# Battery_Charger.net
KiCad netlist of a schematic drawn in EAGLE
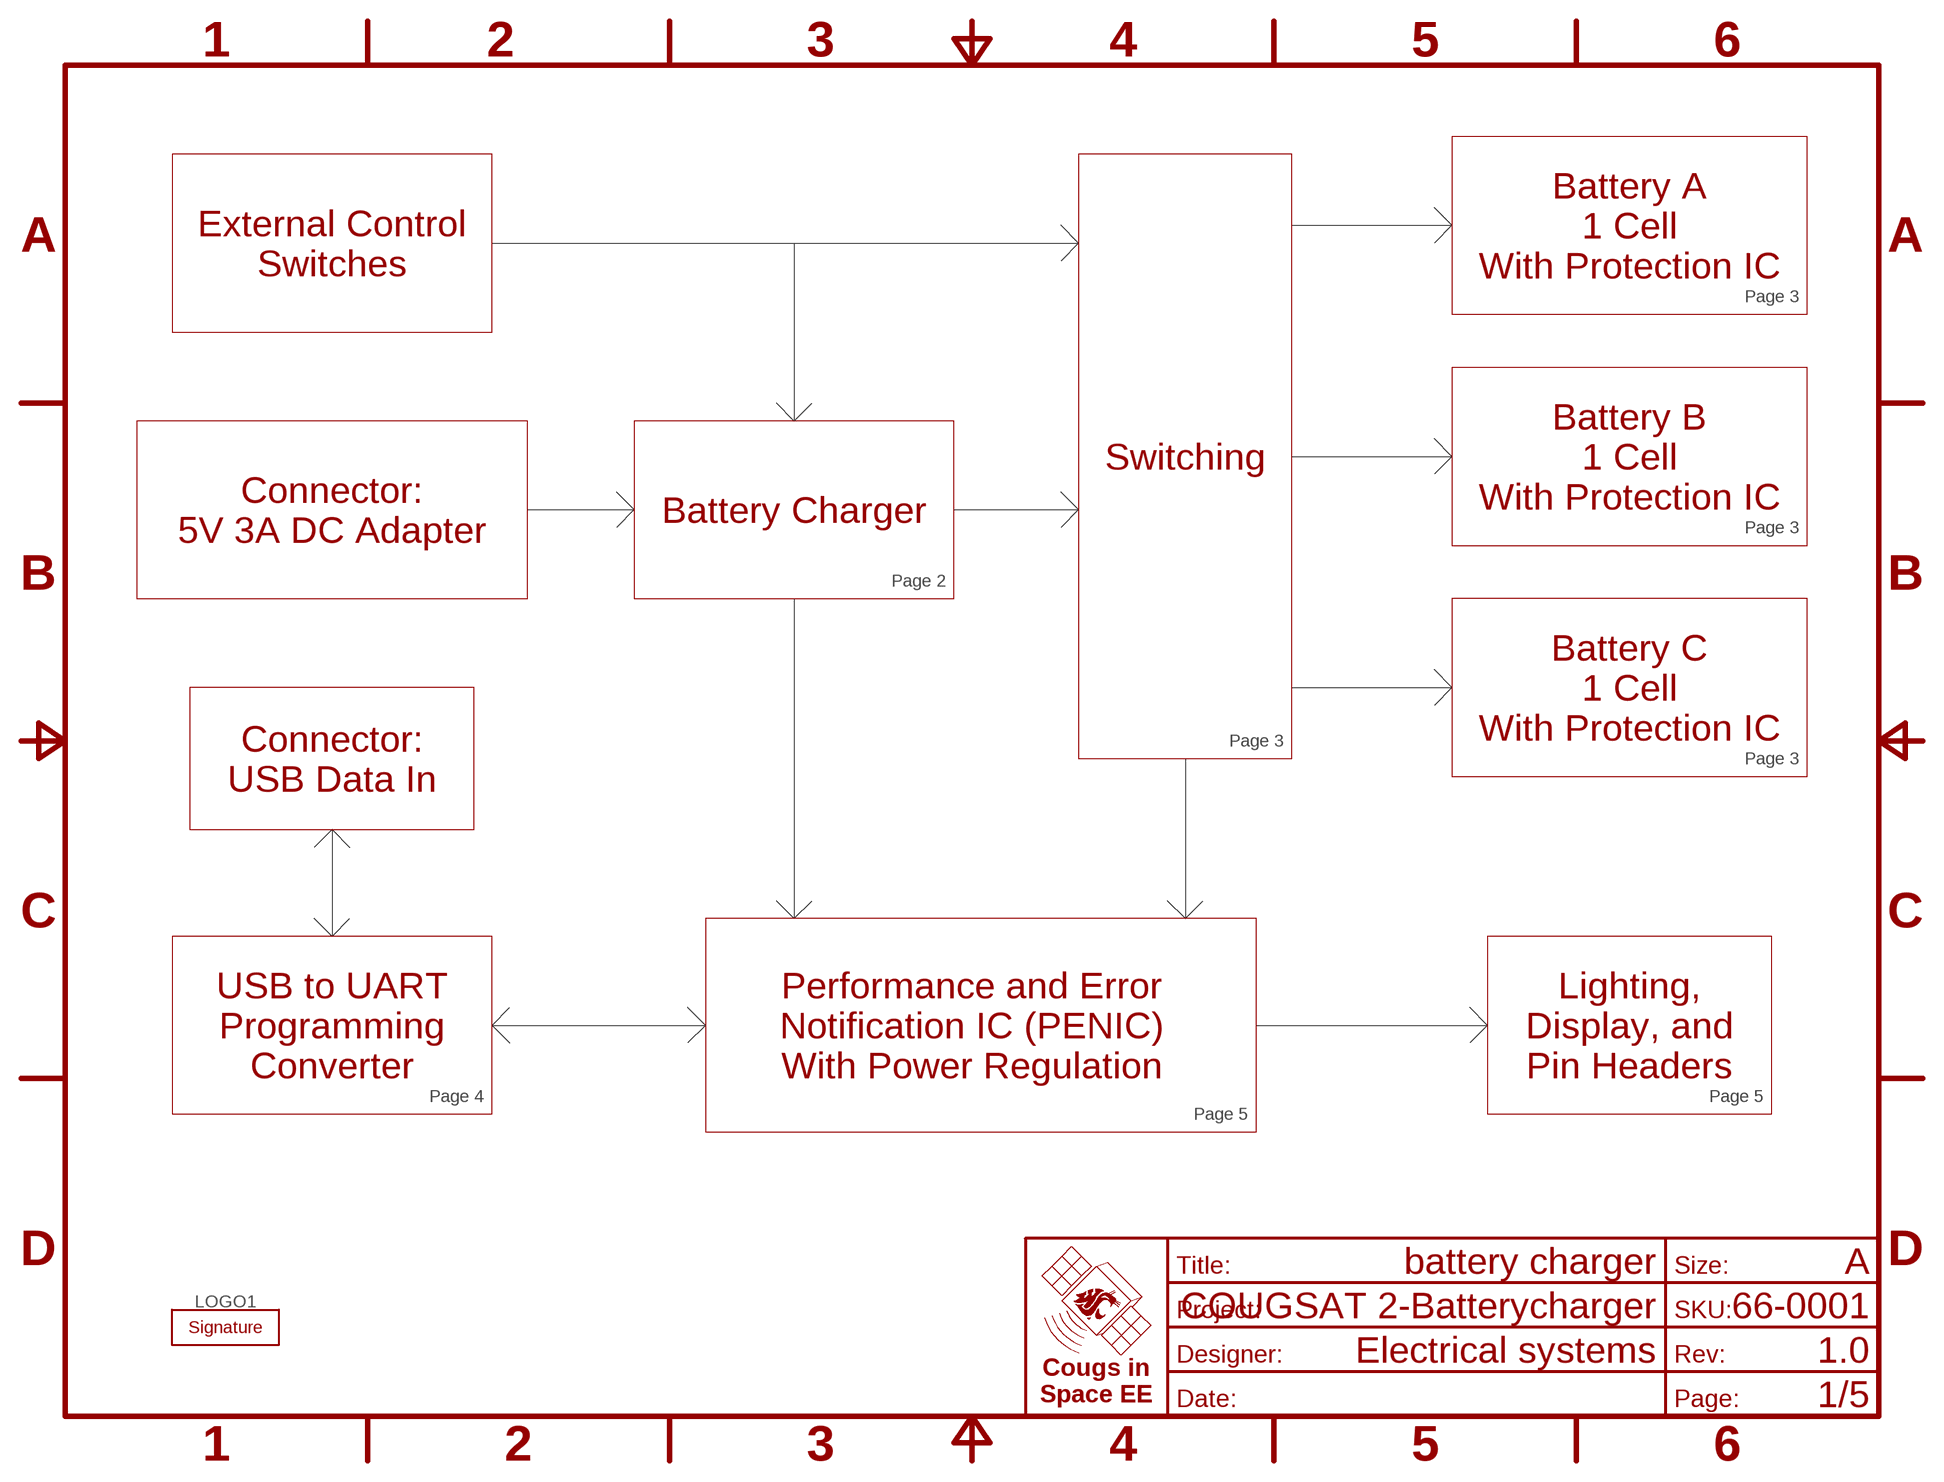
[diagram p0: schematic, sheet 1]
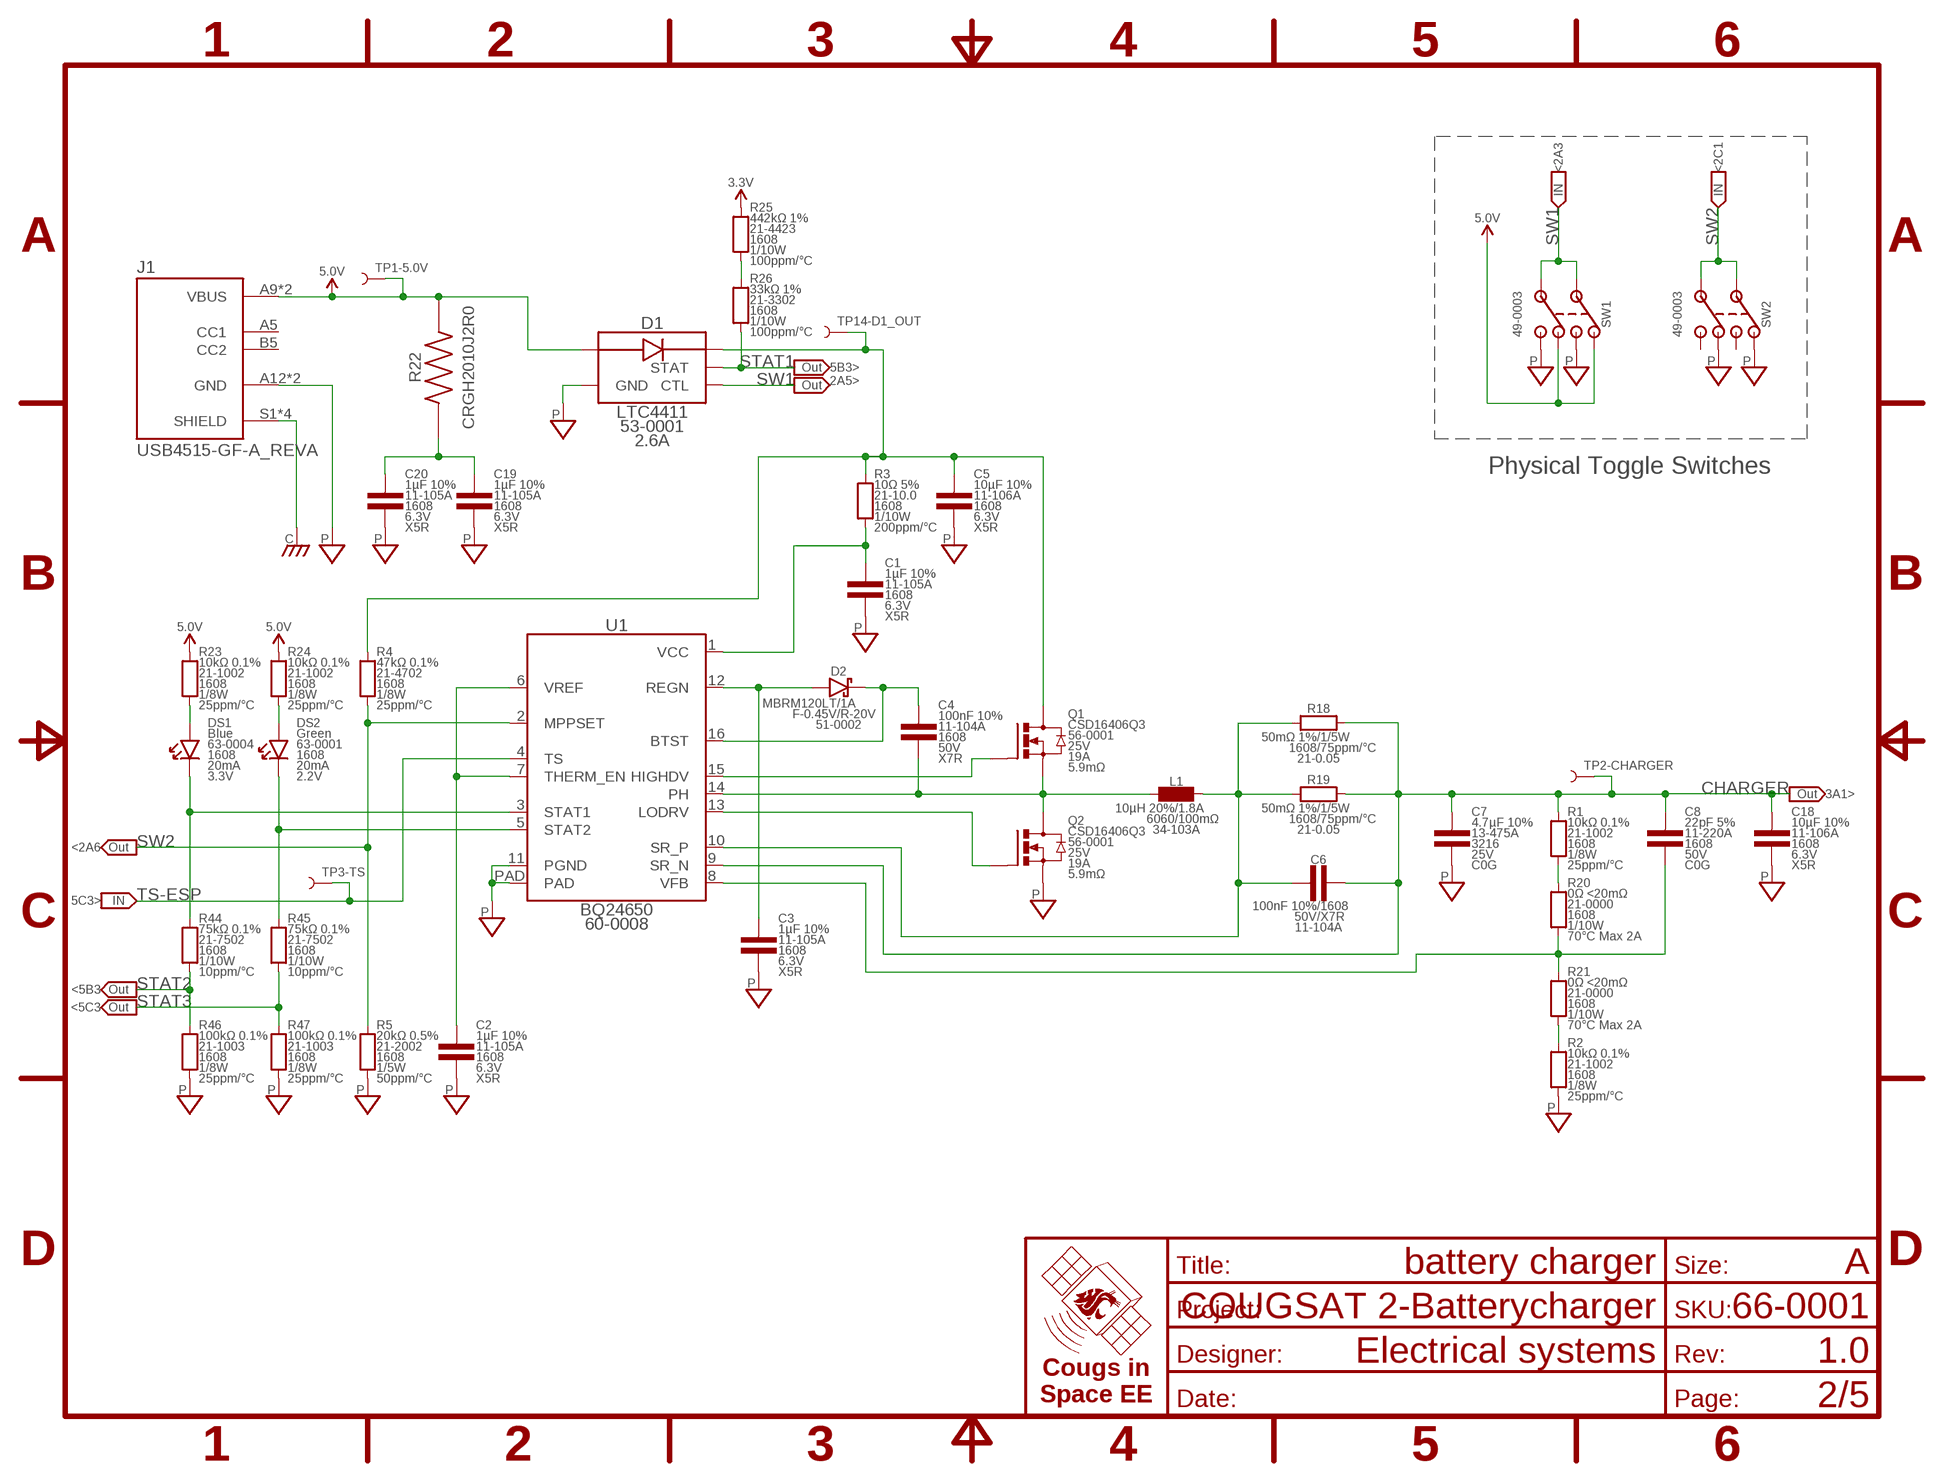
[diagram p1: schematic, sheet 2]
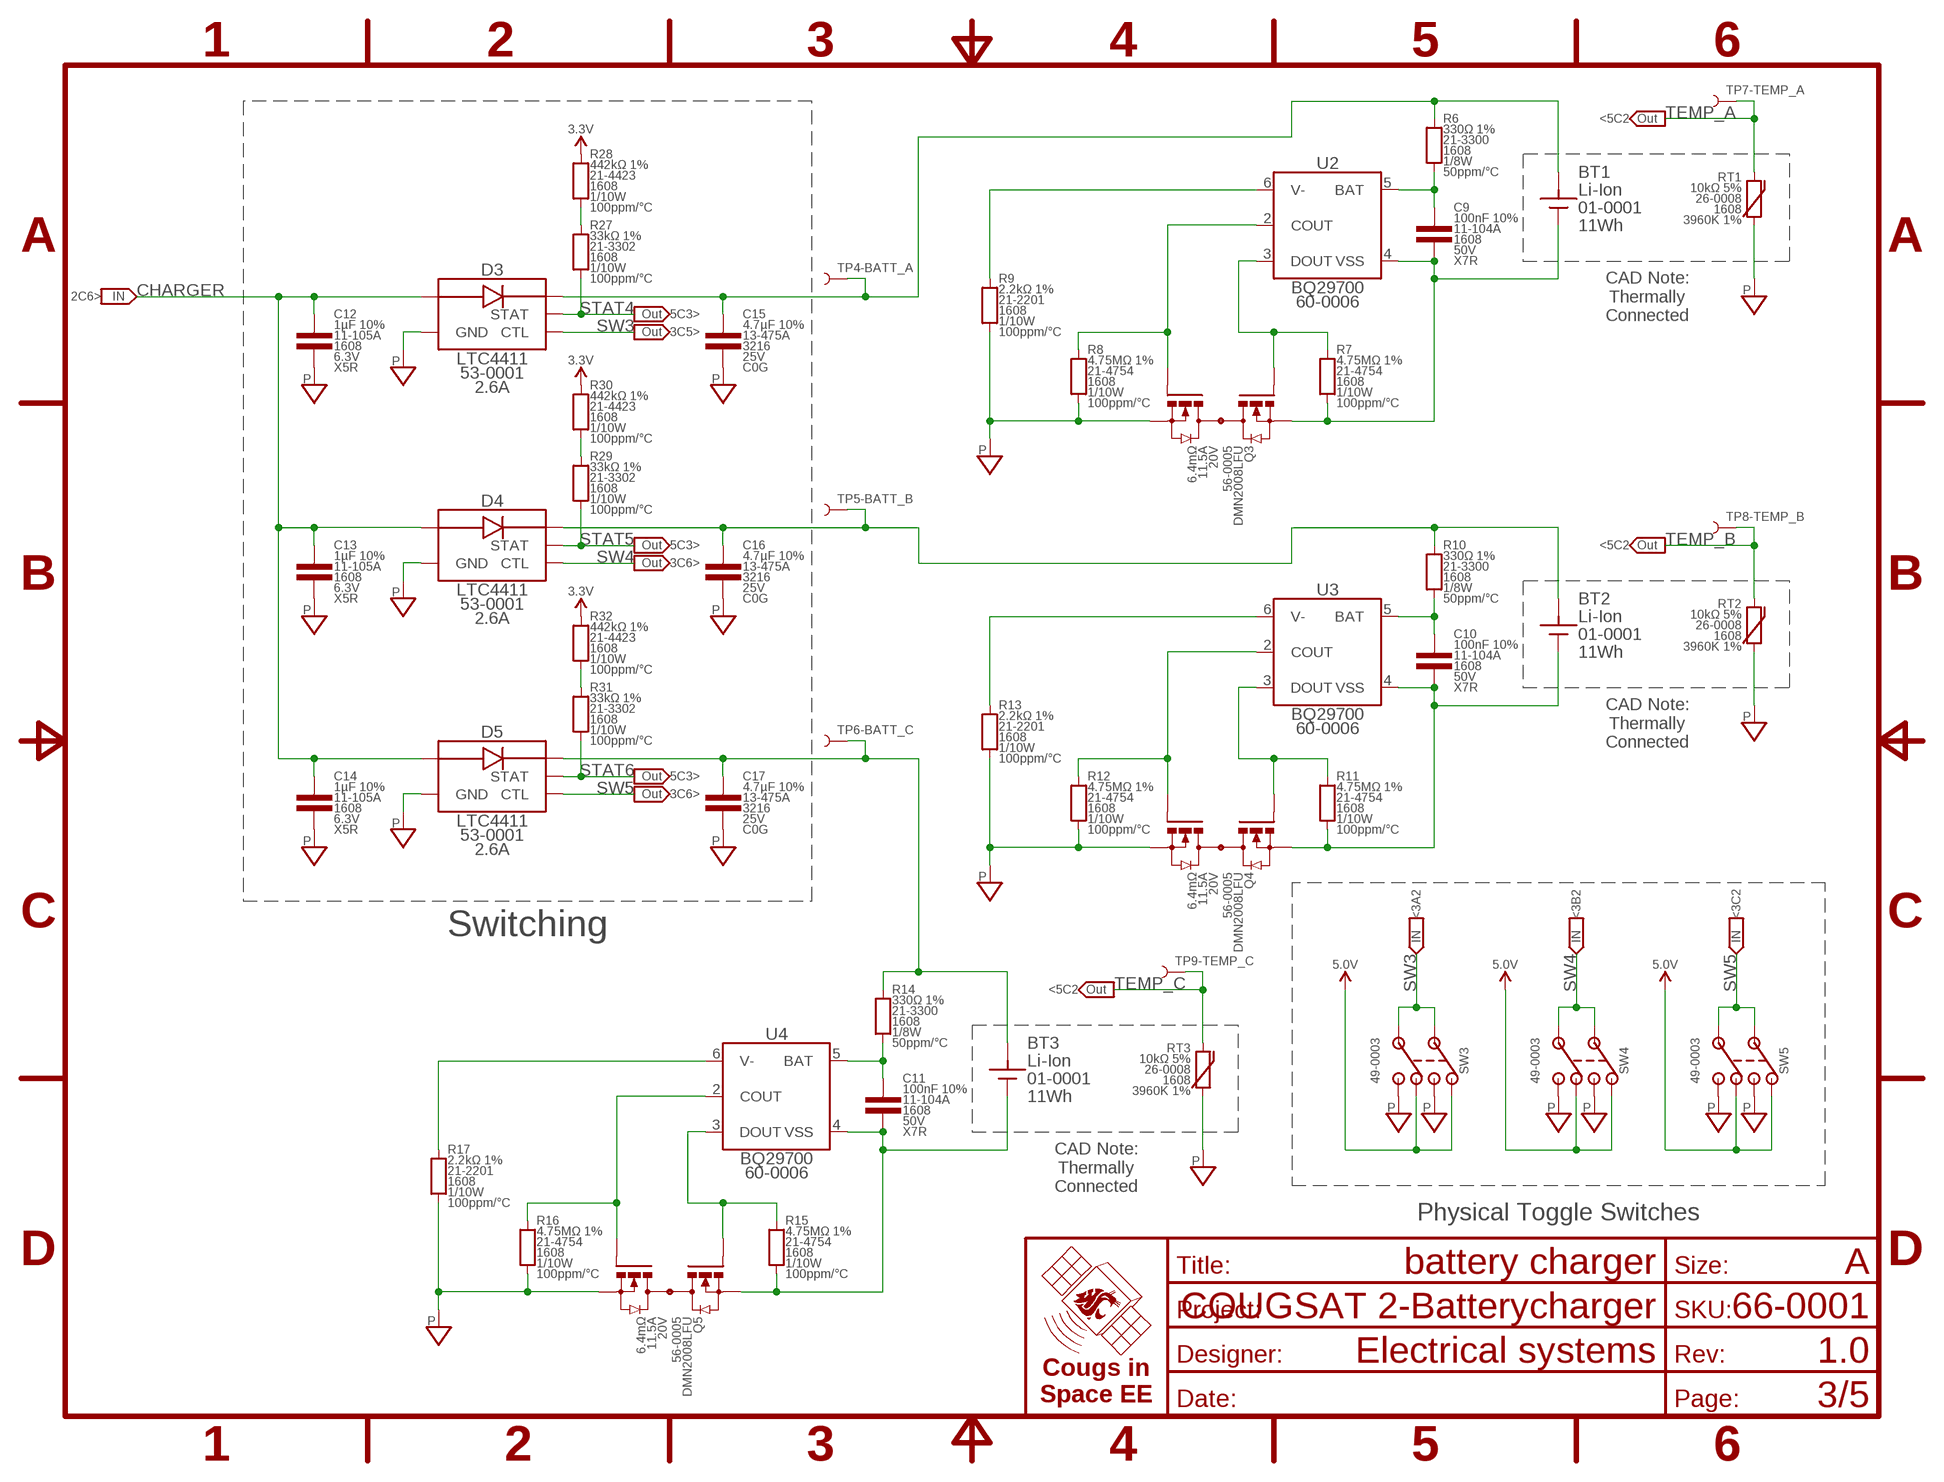
[diagram p2: schematic, sheet 3]
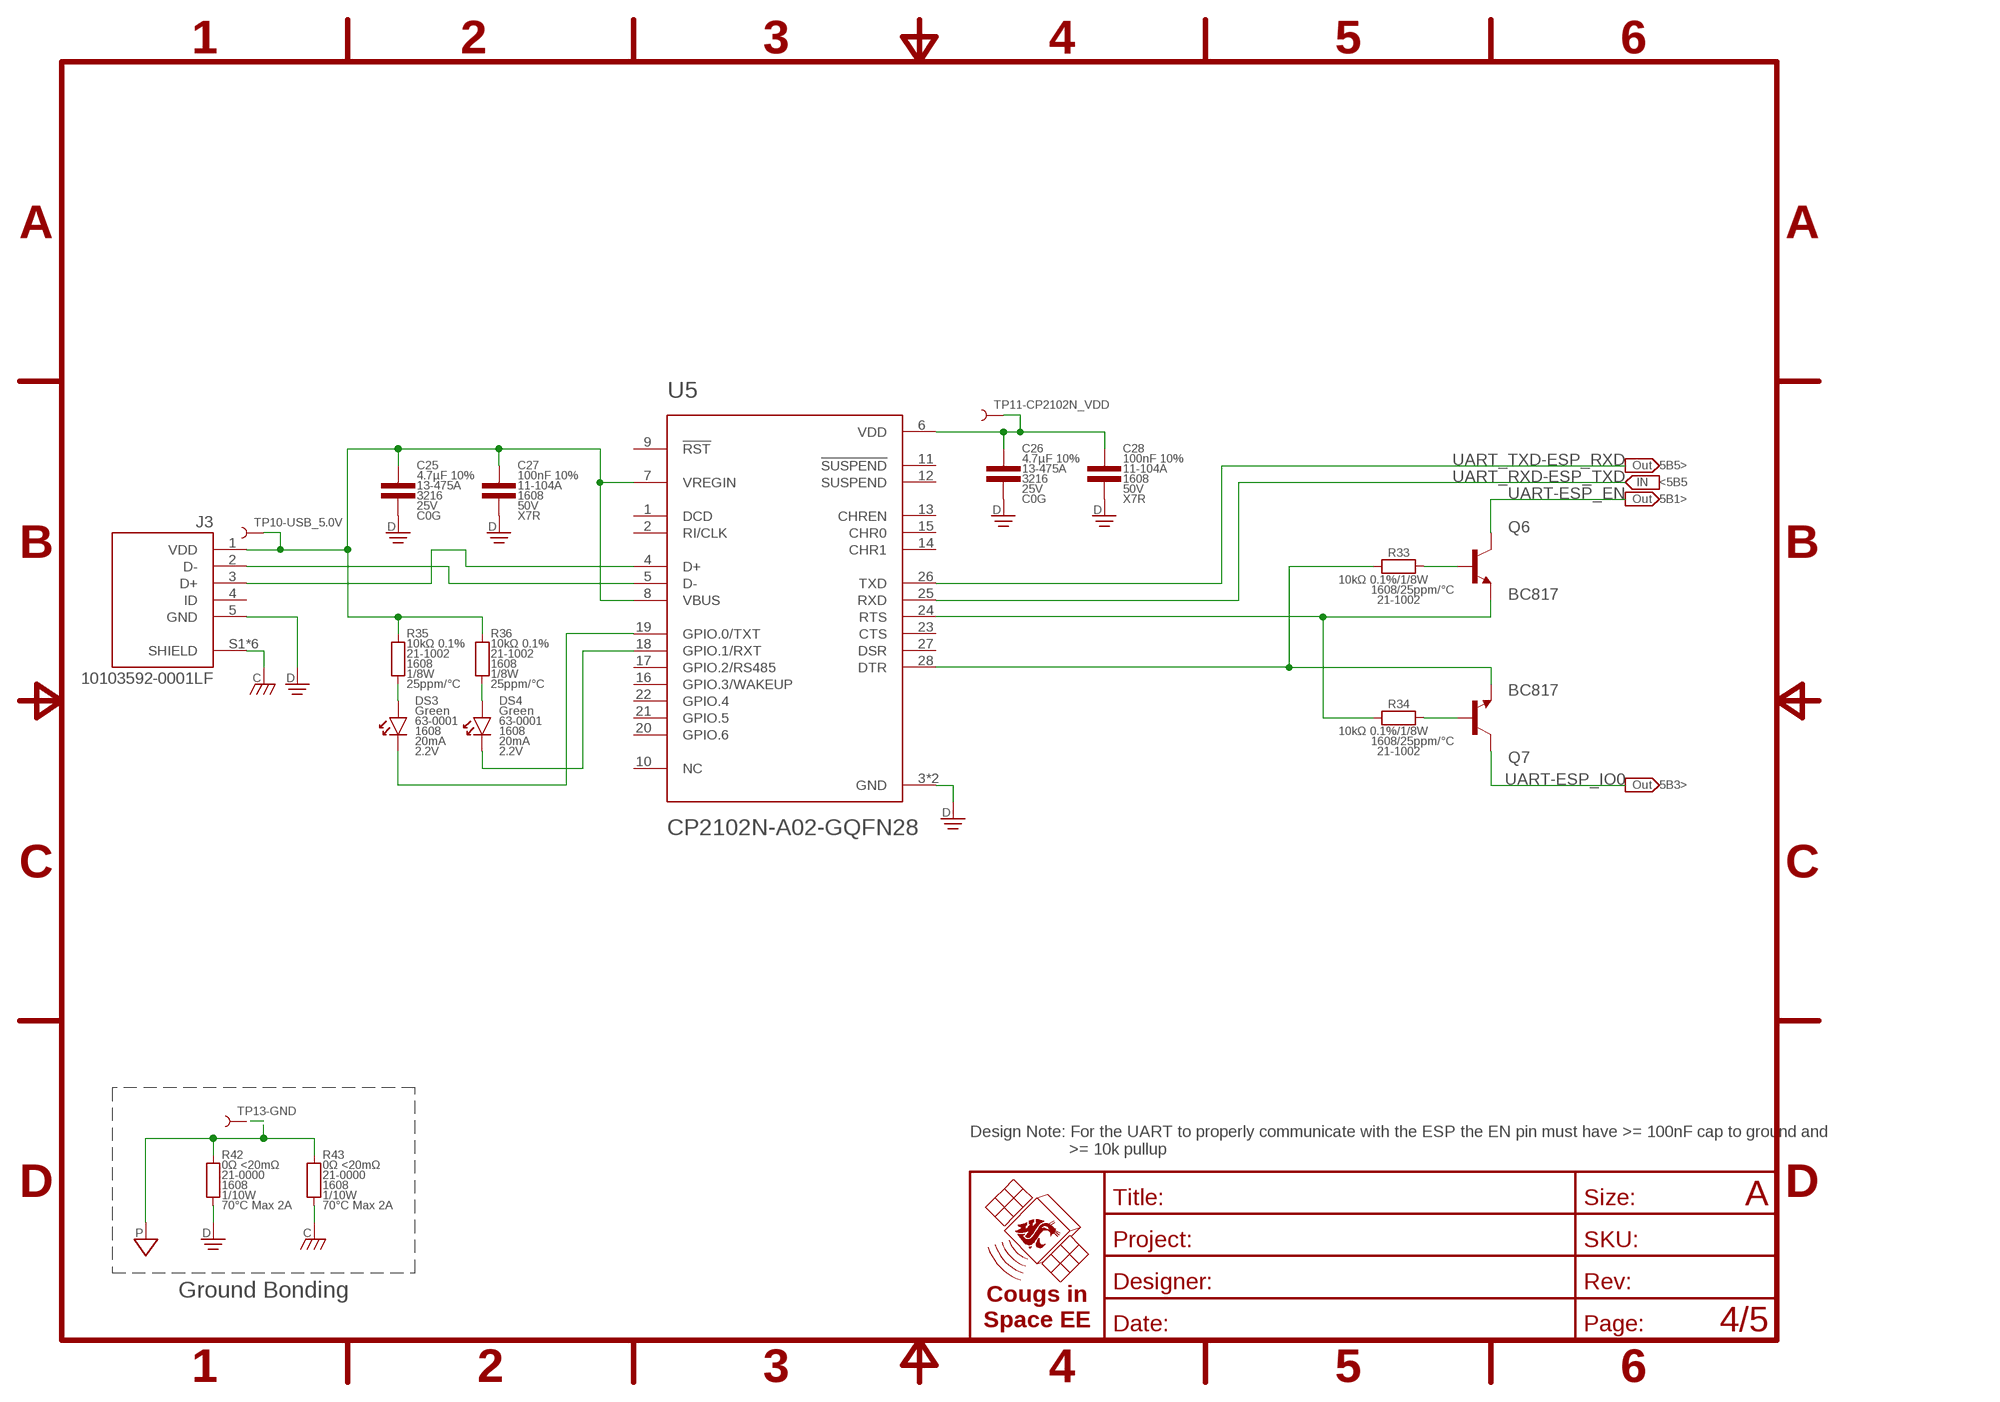
[diagram p3: schematic, sheet 4]
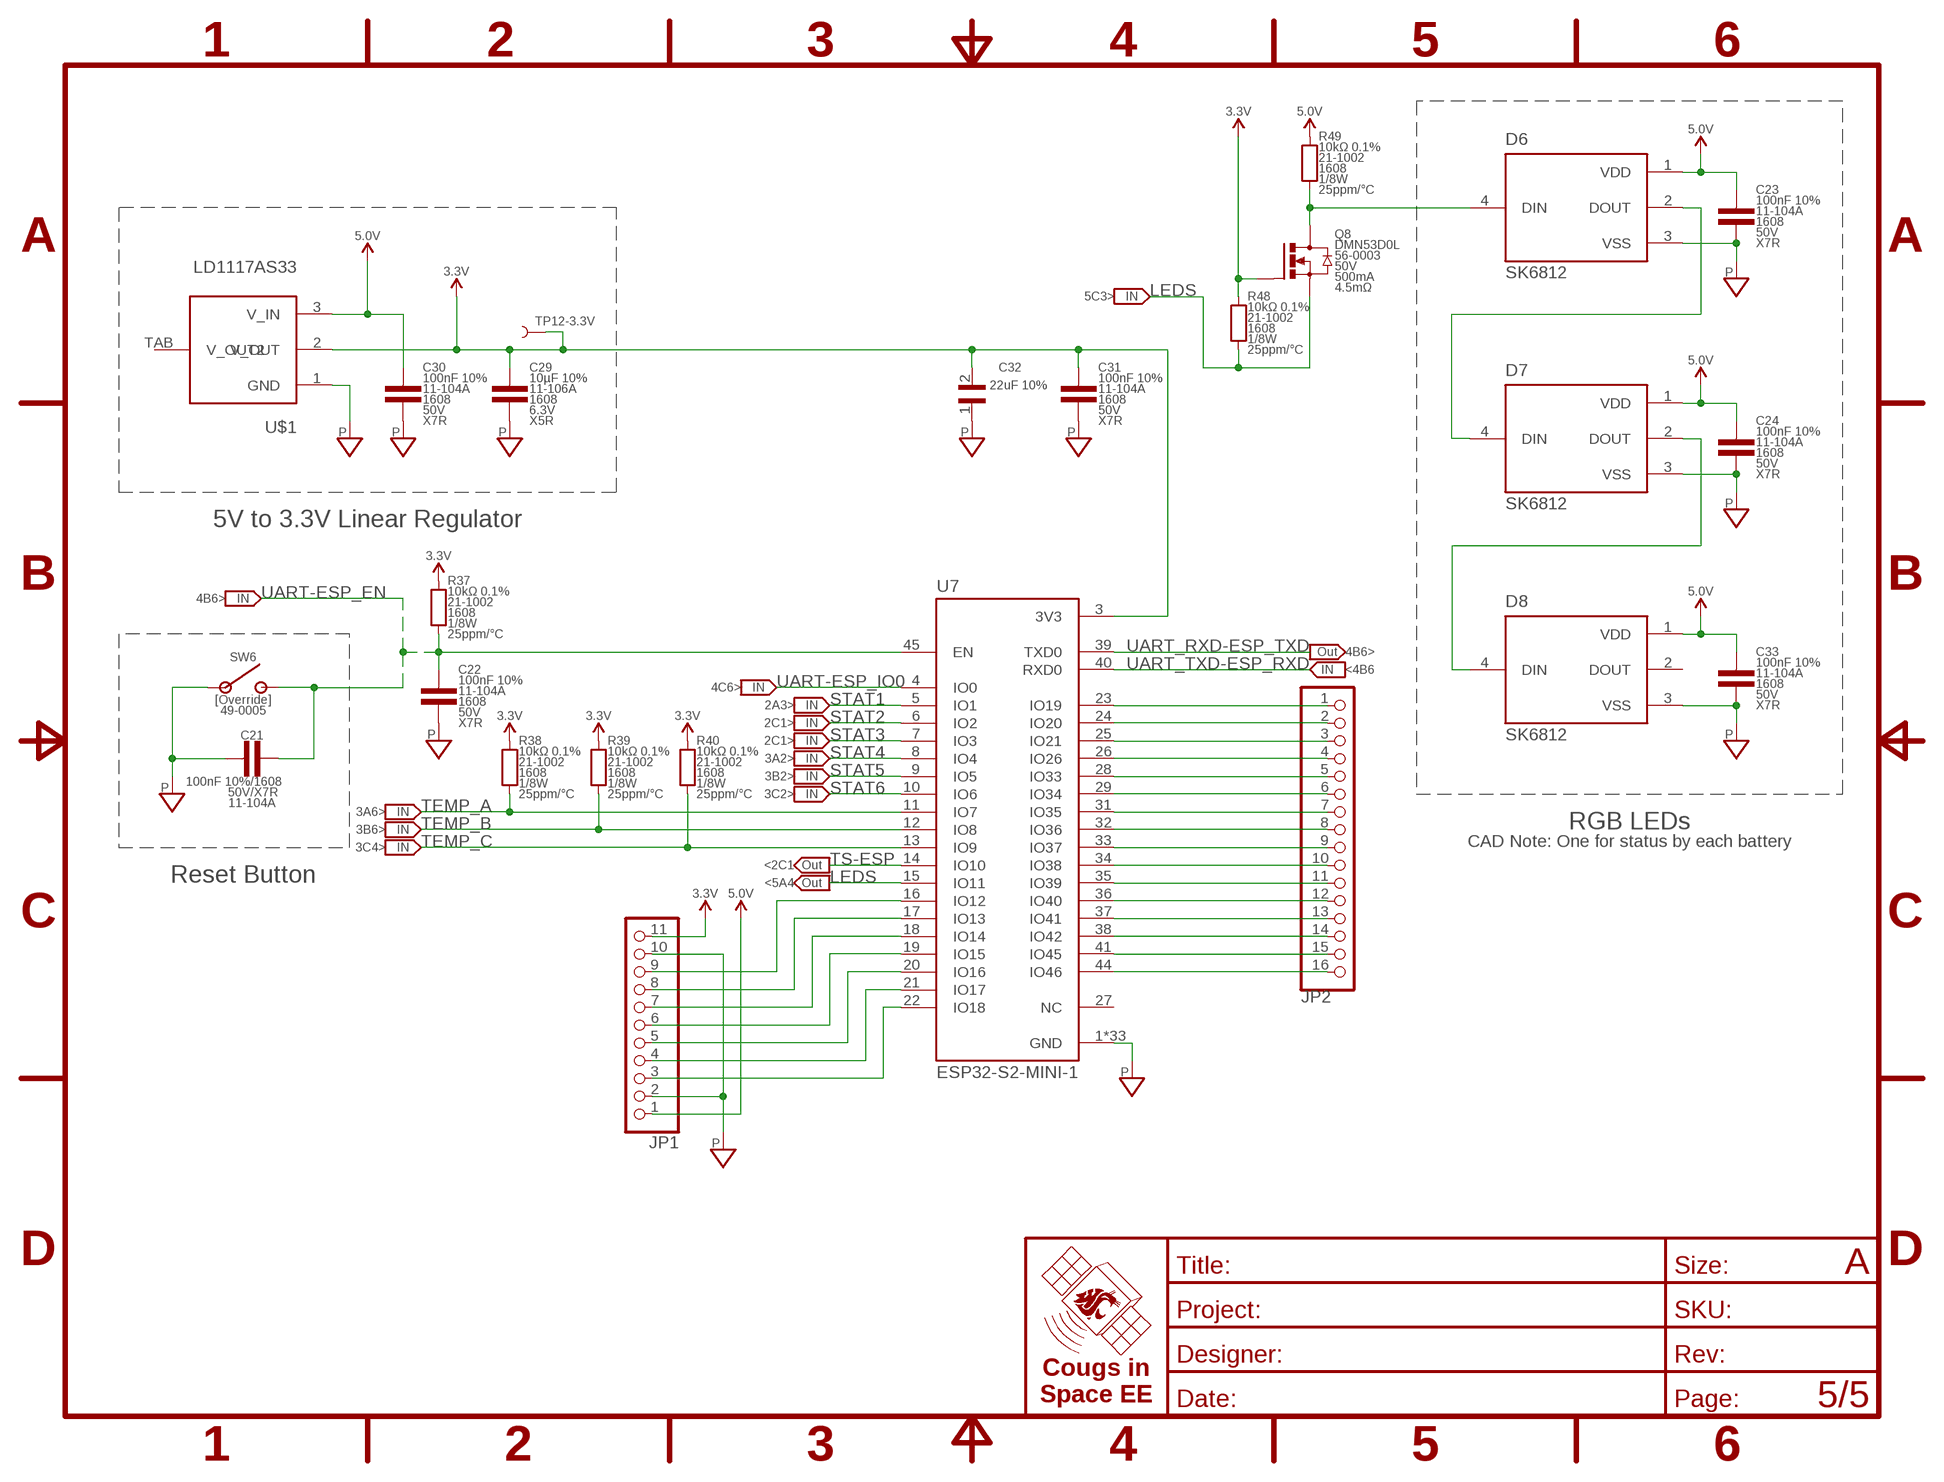
[diagram p4: schematic, sheet 5]

(export (version "E")
  (design (tool "Eeschema 10.0.6"))
  (components
    (comp (ref "LOGO1")
      (value "SIGNATUREZACHARY")
      (footprint "eagle-import:SIGN-ZACHARY")
      (libsource (lib "eagle-import") (part "SIGNATUREZACHARY"))
    )
    (comp (ref "C25")
      (value "4.7µF 10%")
      (footprint "eagle-import:3216")
      (fields
        (field (name "PACKAGE") "3216")
        (field (name "SKU") "13-475A")
        (field (name "TEMP") "C0G")
        (field (name "VOLTAGE") "25V")
      )
      (libsource (lib "eagle-import") (part "CAP-V-3216-4.7UF"))
    )
    (comp (ref "C26")
      (value "4.7µF 10%")
      (footprint "eagle-import:3216")
      (fields
        (field (name "PACKAGE") "3216")
        (field (name "SKU") "13-475A")
        (field (name "TEMP") "C0G")
        (field (name "VOLTAGE") "25V")
      )
      (libsource (lib "eagle-import") (part "CAP-V-3216-4.7UF"))
    )
    (comp (ref "C27")
      (value "100nF 10%")
      (footprint "eagle-import:1608")
      (fields
        (field (name "PACKAGE") "1608")
        (field (name "SKU") "11-104A")
        (field (name "TEMP") "X7R")
        (field (name "VOLTAGE") "50V")
      )
      (libsource (lib "eagle-import") (part "CAP-V-1608-100NF"))
    )
    (comp (ref "C28")
      (value "100nF 10%")
      (footprint "eagle-import:1608")
      (fields
        (field (name "PACKAGE") "1608")
        (field (name "SKU") "11-104A")
        (field (name "TEMP") "X7R")
        (field (name "VOLTAGE") "50V")
      )
      (libsource (lib "eagle-import") (part "CAP-V-1608-100NF"))
    )
    (comp (ref "DS3")
      (value "Green")
      (footprint "eagle-import:1608-POL")
      (fields
        (field (name "CURRENT") "20mA")
        (field (name "PACKAGE") "1608")
        (field (name "SKU") "63-0001")
        (field (name "VF") "2.2V")
      )
      (libsource (lib "eagle-import") (part "LED-V-1608-GRN"))
    )
    (comp (ref "DS4")
      (value "Green")
      (footprint "eagle-import:1608-POL")
      (fields
        (field (name "CURRENT") "20mA")
        (field (name "PACKAGE") "1608")
        (field (name "SKU") "63-0001")
        (field (name "VF") "2.2V")
      )
      (libsource (lib "eagle-import") (part "LED-V-1608-GRN"))
    )
    (comp (ref "J3")
      (value "10103592-0001LF")
      (footprint "eagle-import:AMPHENOL_10103592-0001LF")
      (fields (field (name "MF") "AMPHENOL ICC / FCI"))
      (libsource (lib "eagle-import") (part "10103592-0001LF"))
    )
    (comp (ref "Q6")
      (value "BC817")
      (footprint "eagle-import:SOT95P230X110-3N")
      (fields (field (name "MF") "Rectron"))
      (libsource (lib "eagle-import") (part "BC817"))
    )
    (comp (ref "Q7")
      (value "BC817")
      (footprint "eagle-import:SOT95P230X110-3N")
      (fields (field (name "MF") "Rectron"))
      (libsource (lib "eagle-import") (part "BC817"))
    )
    (comp (ref "R33")
      (value "10kΩ 0.1%")
      (footprint "eagle-import:1608")
      (fields
        (field (name "PACKAGE") "1608")
        (field (name "POWER") "1/8W")
        (field (name "SKU") "21-1002")
        (field (name "TEMP") "25ppm/°C")
      )
      (libsource (lib "eagle-import") (part "RES-H-1608-10K"))
    )
    (comp (ref "R34")
      (value "10kΩ 0.1%")
      (footprint "eagle-import:1608")
      (fields
        (field (name "PACKAGE") "1608")
        (field (name "POWER") "1/8W")
        (field (name "SKU") "21-1002")
        (field (name "TEMP") "25ppm/°C")
      )
      (libsource (lib "eagle-import") (part "RES-H-1608-10K"))
    )
    (comp (ref "R35")
      (value "10kΩ 0.1%")
      (footprint "eagle-import:1608")
      (fields
        (field (name "PACKAGE") "1608")
        (field (name "POWER") "1/8W")
        (field (name "SKU") "21-1002")
        (field (name "TEMP") "25ppm/°C")
      )
      (libsource (lib "eagle-import") (part "RES-V-1608-10K"))
    )
    (comp (ref "R36")
      (value "10kΩ 0.1%")
      (footprint "eagle-import:1608")
      (fields
        (field (name "PACKAGE") "1608")
        (field (name "POWER") "1/8W")
        (field (name "SKU") "21-1002")
        (field (name "TEMP") "25ppm/°C")
      )
      (libsource (lib "eagle-import") (part "RES-V-1608-10K"))
    )
    (comp (ref "R42")
      (value "0Ω <20mΩ")
      (footprint "eagle-import:1608")
      (fields
        (field (name "PACKAGE") "1608")
        (field (name "POWER") "1/10W")
        (field (name "SKU") "21-0000")
        (field (name "TEMP") "70°C Max 2A")
      )
      (libsource (lib "eagle-import") (part "RES-V-1608-0"))
    )
    (comp (ref "R43")
      (value "0Ω <20mΩ")
      (footprint "eagle-import:1608")
      (fields
        (field (name "PACKAGE") "1608")
        (field (name "POWER") "1/10W")
        (field (name "SKU") "21-0000")
        (field (name "TEMP") "70°C Max 2A")
      )
      (libsource (lib "eagle-import") (part "RES-V-1608-0"))
    )
    (comp (ref "TP10-USB_5.0V")
      (value "TEST_POINT-SMD-C-1.25")
      (footprint "eagle-import:SMD-C-1.25")
      (libsource (lib "eagle-import") (part "TEST_POINT-SMD-C-1.25"))
    )
    (comp (ref "TP11-CP2102N_VDD")
      (value "TEST_POINT-SMD-C-1.25")
      (footprint "eagle-import:SMD-C-1.25")
      (libsource (lib "eagle-import") (part "TEST_POINT-SMD-C-1.25"))
    )
    (comp (ref "TP13-GND")
      (value "TEST_POINT-SMD-C-1.25")
      (footprint "eagle-import:SMD-C-1.25")
      (libsource (lib "eagle-import") (part "TEST_POINT-SMD-C-1.25"))
    )
    (comp (ref "U5")
      (value "CP2102N-A02-GQFN28")
      (footprint "eagle-import:QFN50P500X500X80-29N")
      (fields (field (name "MF") "Silicon Labs"))
      (libsource (lib "eagle-import") (part "CP2102N-A02-GQFN28"))
    )
    (comp (ref "BT1")
      (value "Li-Ion")
      (footprint "eagle-import:18650-SOLDERED")
      (fields (field (name "CAPACITY") "11Wh") (field (name "SKU") "01-0001"))
      (libsource (lib "eagle-import") (part "BATTERY-?18650HG2"))
    )
    (comp (ref "BT2")
      (value "Li-Ion")
      (footprint "eagle-import:18650-SOLDERED")
      (fields (field (name "CAPACITY") "11Wh") (field (name "SKU") "01-0001"))
      (libsource (lib "eagle-import") (part "BATTERY-?18650HG2"))
    )
    (comp (ref "BT3")
      (value "Li-Ion")
      (footprint "eagle-import:18650-SOLDERED")
      (fields (field (name "CAPACITY") "11Wh") (field (name "SKU") "01-0001"))
      (libsource (lib "eagle-import") (part "BATTERY-?18650HG2"))
    )
    (comp (ref "C9")
      (value "100nF 10%")
      (footprint "eagle-import:1608")
      (fields
        (field (name "PACKAGE") "1608")
        (field (name "SKU") "11-104A")
        (field (name "TEMP") "X7R")
        (field (name "VOLTAGE") "50V")
      )
      (libsource (lib "eagle-import") (part "CAP-V-1608-100NF"))
    )
    (comp (ref "C10")
      (value "100nF 10%")
      (footprint "eagle-import:1608")
      (fields
        (field (name "PACKAGE") "1608")
        (field (name "SKU") "11-104A")
        (field (name "TEMP") "X7R")
        (field (name "VOLTAGE") "50V")
      )
      (libsource (lib "eagle-import") (part "CAP-V-1608-100NF"))
    )
    (comp (ref "C11")
      (value "100nF 10%")
      (footprint "eagle-import:1608")
      (fields
        (field (name "PACKAGE") "1608")
        (field (name "SKU") "11-104A")
        (field (name "TEMP") "X7R")
        (field (name "VOLTAGE") "50V")
      )
      (libsource (lib "eagle-import") (part "CAP-V-1608-100NF"))
    )
    (comp (ref "C12")
      (value "1µF 10%")
      (footprint "eagle-import:1608")
      (fields
        (field (name "PACKAGE") "1608")
        (field (name "SKU") "11-105A")
        (field (name "TEMP") "X5R")
        (field (name "VOLTAGE") "6.3V")
      )
      (libsource (lib "eagle-import") (part "CAP-V-1608-1UF"))
    )
    (comp (ref "C13")
      (value "1µF 10%")
      (footprint "eagle-import:1608")
      (fields
        (field (name "PACKAGE") "1608")
        (field (name "SKU") "11-105A")
        (field (name "TEMP") "X5R")
        (field (name "VOLTAGE") "6.3V")
      )
      (libsource (lib "eagle-import") (part "CAP-V-1608-1UF"))
    )
    (comp (ref "C14")
      (value "1µF 10%")
      (footprint "eagle-import:1608")
      (fields
        (field (name "PACKAGE") "1608")
        (field (name "SKU") "11-105A")
        (field (name "TEMP") "X5R")
        (field (name "VOLTAGE") "6.3V")
      )
      (libsource (lib "eagle-import") (part "CAP-V-1608-1UF"))
    )
    (comp (ref "C15")
      (value "4.7µF 10%")
      (footprint "eagle-import:3216")
      (fields
        (field (name "PACKAGE") "3216")
        (field (name "SKU") "13-475A")
        (field (name "TEMP") "C0G")
        (field (name "VOLTAGE") "25V")
      )
      (libsource (lib "eagle-import") (part "CAP-V-3216-4.7UF"))
    )
    (comp (ref "C16")
      (value "4.7µF 10%")
      (footprint "eagle-import:3216")
      (fields
        (field (name "PACKAGE") "3216")
        (field (name "SKU") "13-475A")
        (field (name "TEMP") "C0G")
        (field (name "VOLTAGE") "25V")
      )
      (libsource (lib "eagle-import") (part "CAP-V-3216-4.7UF"))
    )
    (comp (ref "C17")
      (value "4.7µF 10%")
      (footprint "eagle-import:3216")
      (fields
        (field (name "PACKAGE") "3216")
        (field (name "SKU") "13-475A")
        (field (name "TEMP") "C0G")
        (field (name "VOLTAGE") "25V")
      )
      (libsource (lib "eagle-import") (part "CAP-V-3216-4.7UF"))
    )
    (comp (ref "D3")
      (value "LTC4411")
      (footprint "eagle-import:SOT23-5")
      (fields (field (name "SKU") "53-0001") (field (name "CURRENT") "2.6A"))
      (libsource (lib "eagle-import") (part "LTC4411"))
    )
    (comp (ref "D4")
      (value "LTC4411")
      (footprint "eagle-import:SOT23-5")
      (fields (field (name "SKU") "53-0001") (field (name "CURRENT") "2.6A"))
      (libsource (lib "eagle-import") (part "LTC4411"))
    )
    (comp (ref "D5")
      (value "LTC4411")
      (footprint "eagle-import:SOT23-5")
      (fields (field (name "SKU") "53-0001") (field (name "CURRENT") "2.6A"))
      (libsource (lib "eagle-import") (part "LTC4411"))
    )
    (comp (ref "Q3")
      (value "DMN2008LFU")
      (footprint "eagle-import:UDFN-6-B")
      (fields
        (field (name "CURRENT") "11.5A")
        (field (name "RDS") "6.4mΩ")
        (field (name "SKU") "56-0005")
        (field (name "VDS") "20V")
      )
      (libsource (lib "eagle-import") (part "MOSFET_DUAL_COM_D-N-UDFN-6-B-DMN2008LFU"))
    )
    (comp (ref "Q4")
      (value "DMN2008LFU")
      (footprint "eagle-import:UDFN-6-B")
      (fields
        (field (name "CURRENT") "11.5A")
        (field (name "RDS") "6.4mΩ")
        (field (name "SKU") "56-0005")
        (field (name "VDS") "20V")
      )
      (libsource (lib "eagle-import") (part "MOSFET_DUAL_COM_D-N-UDFN-6-B-DMN2008LFU"))
    )
    (comp (ref "Q5")
      (value "DMN2008LFU")
      (footprint "eagle-import:UDFN-6-B")
      (fields
        (field (name "CURRENT") "11.5A")
        (field (name "RDS") "6.4mΩ")
        (field (name "SKU") "56-0005")
        (field (name "VDS") "20V")
      )
      (libsource (lib "eagle-import") (part "MOSFET_DUAL_COM_D-N-UDFN-6-B-DMN2008LFU"))
    )
    (comp (ref "R6")
      (value "330Ω 1%")
      (footprint "eagle-import:1608")
      (fields
        (field (name "PACKAGE") "1608")
        (field (name "POWER") "1/8W")
        (field (name "SKU") "21-3300")
        (field (name "TEMP") "50ppm/°C")
      )
      (libsource (lib "eagle-import") (part "RES-V-1608-330R"))
    )
    (comp (ref "R7")
      (value "4.75MΩ 1%")
      (footprint "eagle-import:1608")
      (fields
        (field (name "PACKAGE") "1608")
        (field (name "POWER") "1/10W")
        (field (name "SKU") "21-4754")
        (field (name "TEMP") "100ppm/°C")
      )
      (libsource (lib "eagle-import") (part "RES-V-1608-4.75M"))
    )
    (comp (ref "R8")
      (value "4.75MΩ 1%")
      (footprint "eagle-import:1608")
      (fields
        (field (name "PACKAGE") "1608")
        (field (name "POWER") "1/10W")
        (field (name "SKU") "21-4754")
        (field (name "TEMP") "100ppm/°C")
      )
      (libsource (lib "eagle-import") (part "RES-V-1608-4.75M"))
    )
    (comp (ref "R9")
      (value "2.2kΩ 1%")
      (footprint "eagle-import:1608")
      (fields
        (field (name "PACKAGE") "1608")
        (field (name "POWER") "1/10W")
        (field (name "SKU") "21-2201")
        (field (name "TEMP") "100ppm/°C")
      )
      (libsource (lib "eagle-import") (part "RES-V-1608-2.2K"))
    )
    (comp (ref "R10")
      (value "330Ω 1%")
      (footprint "eagle-import:1608")
      (fields
        (field (name "PACKAGE") "1608")
        (field (name "POWER") "1/8W")
        (field (name "SKU") "21-3300")
        (field (name "TEMP") "50ppm/°C")
      )
      (libsource (lib "eagle-import") (part "RES-V-1608-330R"))
    )
    (comp (ref "R11")
      (value "4.75MΩ 1%")
      (footprint "eagle-import:1608")
      (fields
        (field (name "PACKAGE") "1608")
        (field (name "POWER") "1/10W")
        (field (name "SKU") "21-4754")
        (field (name "TEMP") "100ppm/°C")
      )
      (libsource (lib "eagle-import") (part "RES-V-1608-4.75M"))
    )
    (comp (ref "R12")
      (value "4.75MΩ 1%")
      (footprint "eagle-import:1608")
      (fields
        (field (name "PACKAGE") "1608")
        (field (name "POWER") "1/10W")
        (field (name "SKU") "21-4754")
        (field (name "TEMP") "100ppm/°C")
      )
      (libsource (lib "eagle-import") (part "RES-V-1608-4.75M"))
    )
    (comp (ref "R13")
      (value "2.2kΩ 1%")
      (footprint "eagle-import:1608")
      (fields
        (field (name "PACKAGE") "1608")
        (field (name "POWER") "1/10W")
        (field (name "SKU") "21-2201")
        (field (name "TEMP") "100ppm/°C")
      )
      (libsource (lib "eagle-import") (part "RES-V-1608-2.2K"))
    )
    (comp (ref "R14")
      (value "330Ω 1%")
      (footprint "eagle-import:1608")
      (fields
        (field (name "PACKAGE") "1608")
        (field (name "POWER") "1/8W")
        (field (name "SKU") "21-3300")
        (field (name "TEMP") "50ppm/°C")
      )
      (libsource (lib "eagle-import") (part "RES-V-1608-330R"))
    )
    (comp (ref "R15")
      (value "4.75MΩ 1%")
      (footprint "eagle-import:1608")
      (fields
        (field (name "PACKAGE") "1608")
        (field (name "POWER") "1/10W")
        (field (name "SKU") "21-4754")
        (field (name "TEMP") "100ppm/°C")
      )
      (libsource (lib "eagle-import") (part "RES-V-1608-4.75M"))
    )
    (comp (ref "R16")
      (value "4.75MΩ 1%")
      (footprint "eagle-import:1608")
      (fields
        (field (name "PACKAGE") "1608")
        (field (name "POWER") "1/10W")
        (field (name "SKU") "21-4754")
        (field (name "TEMP") "100ppm/°C")
      )
      (libsource (lib "eagle-import") (part "RES-V-1608-4.75M"))
    )
    (comp (ref "R17")
      (value "2.2kΩ 1%")
      (footprint "eagle-import:1608")
      (fields
        (field (name "PACKAGE") "1608")
        (field (name "POWER") "1/10W")
        (field (name "SKU") "21-2201")
        (field (name "TEMP") "100ppm/°C")
      )
      (libsource (lib "eagle-import") (part "RES-V-1608-2.2K"))
    )
    (comp (ref "R27")
      (value "33kΩ 1%")
      (footprint "eagle-import:1608")
      (fields
        (field (name "PACKAGE") "1608")
        (field (name "POWER") "1/10W")
        (field (name "SKU") "21-3302")
        (field (name "TEMP") "100ppm/°C")
      )
      (libsource (lib "eagle-import") (part "RES-V-1608-33K"))
    )
    (comp (ref "R28")
      (value "442kΩ 1%")
      (footprint "eagle-import:1608")
      (fields
        (field (name "PACKAGE") "1608")
        (field (name "POWER") "1/10W")
        (field (name "SKU") "21-4423")
        (field (name "TEMP") "100ppm/°C")
      )
      (libsource (lib "eagle-import") (part "RES-V-1608-442K"))
    )
    (comp (ref "R29")
      (value "33kΩ 1%")
      (footprint "eagle-import:1608")
      (fields
        (field (name "PACKAGE") "1608")
        (field (name "POWER") "1/10W")
        (field (name "SKU") "21-3302")
        (field (name "TEMP") "100ppm/°C")
      )
      (libsource (lib "eagle-import") (part "RES-V-1608-33K"))
    )
    (comp (ref "R30")
      (value "442kΩ 1%")
      (footprint "eagle-import:1608")
      (fields
        (field (name "PACKAGE") "1608")
        (field (name "POWER") "1/10W")
        (field (name "SKU") "21-4423")
        (field (name "TEMP") "100ppm/°C")
      )
      (libsource (lib "eagle-import") (part "RES-V-1608-442K"))
    )
    (comp (ref "R31")
      (value "33kΩ 1%")
      (footprint "eagle-import:1608")
      (fields
        (field (name "PACKAGE") "1608")
        (field (name "POWER") "1/10W")
        (field (name "SKU") "21-3302")
        (field (name "TEMP") "100ppm/°C")
      )
      (libsource (lib "eagle-import") (part "RES-V-1608-33K"))
    )
    (comp (ref "R32")
      (value "442kΩ 1%")
      (footprint "eagle-import:1608")
      (fields
        (field (name "PACKAGE") "1608")
        (field (name "POWER") "1/10W")
        (field (name "SKU") "21-4423")
        (field (name "TEMP") "100ppm/°C")
      )
      (libsource (lib "eagle-import") (part "RES-V-1608-442K"))
    )
    (comp (ref "RT1")
      (value "10kΩ 5%")
      (footprint "eagle-import:1608")
      (fields
        (field (name "B2585") "3960K 1%")
        (field (name "PACKAGE") "1608")
        (field (name "SKU") "26-0008")
      )
      (libsource (lib "eagle-import") (part "THERMISTOR-V-1608-10K"))
    )
    (comp (ref "RT2")
      (value "10kΩ 5%")
      (footprint "eagle-import:1608")
      (fields
        (field (name "B2585") "3960K 1%")
        (field (name "PACKAGE") "1608")
        (field (name "SKU") "26-0008")
      )
      (libsource (lib "eagle-import") (part "THERMISTOR-V-1608-10K"))
    )
    (comp (ref "RT3")
      (value "10kΩ 5%")
      (footprint "eagle-import:1608")
      (fields
        (field (name "B2585") "3960K 1%")
        (field (name "PACKAGE") "1608")
        (field (name "SKU") "26-0008")
      )
      (libsource (lib "eagle-import") (part "THERMISTOR-V-1608-10K"))
    )
    (comp (ref "SW3")
      (value "SWITCH-DPDT-100DP1T1B1M2QE")
      (footprint "eagle-import:100DP1T1B1M2QE")
      (fields (field (name "SKU") "49-0003"))
      (libsource (lib "eagle-import") (part "SWITCH-DPDT-100DP1T1B1M2QE"))
    )
    (comp (ref "SW4")
      (value "SWITCH-DPDT-100DP1T1B1M2QE")
      (footprint "eagle-import:100DP1T1B1M2QE")
      (fields (field (name "SKU") "49-0003"))
      (libsource (lib "eagle-import") (part "SWITCH-DPDT-100DP1T1B1M2QE"))
    )
    (comp (ref "SW5")
      (value "SWITCH-DPDT-100DP1T1B1M2QE")
      (footprint "eagle-import:100DP1T1B1M2QE")
      (fields (field (name "SKU") "49-0003"))
      (libsource (lib "eagle-import") (part "SWITCH-DPDT-100DP1T1B1M2QE"))
    )
    (comp (ref "TP4-BATT_A")
      (value "TEST_POINT-SMD-C-1.25")
      (footprint "eagle-import:SMD-C-1.25")
      (libsource (lib "eagle-import") (part "TEST_POINT-SMD-C-1.25"))
    )
    (comp (ref "TP5-BATT_B")
      (value "TEST_POINT-SMD-C-1.25")
      (footprint "eagle-import:SMD-C-1.25")
      (libsource (lib "eagle-import") (part "TEST_POINT-SMD-C-1.25"))
    )
    (comp (ref "TP6-BATT_C")
      (value "TEST_POINT-SMD-C-1.25")
      (footprint "eagle-import:SMD-C-1.25")
      (libsource (lib "eagle-import") (part "TEST_POINT-SMD-C-1.25"))
    )
    (comp (ref "TP7-TEMP_A")
      (value "TEST_POINT-SMD-C-1.25")
      (footprint "eagle-import:SMD-C-1.25")
      (libsource (lib "eagle-import") (part "TEST_POINT-SMD-C-1.25"))
    )
    (comp (ref "TP8-TEMP_B")
      (value "TEST_POINT-SMD-C-1.25")
      (footprint "eagle-import:SMD-C-1.25")
      (libsource (lib "eagle-import") (part "TEST_POINT-SMD-C-1.25"))
    )
    (comp (ref "TP9-TEMP_C")
      (value "TEST_POINT-SMD-C-1.25")
      (footprint "eagle-import:SMD-C-1.25")
      (libsource (lib "eagle-import") (part "TEST_POINT-SMD-C-1.25"))
    )
    (comp (ref "U2")
      (value "BQ29700")
      (footprint "eagle-import:WSON-6")
      (fields (field (name "SKU") "60-0006"))
      (libsource (lib "eagle-import") (part "BQ29700"))
    )
    (comp (ref "U3")
      (value "BQ29700")
      (footprint "eagle-import:WSON-6")
      (fields (field (name "SKU") "60-0006"))
      (libsource (lib "eagle-import") (part "BQ29700"))
    )
    (comp (ref "U4")
      (value "BQ29700")
      (footprint "eagle-import:WSON-6")
      (fields (field (name "SKU") "60-0006"))
      (libsource (lib "eagle-import") (part "BQ29700"))
    )
    (comp (ref "C21")
      (value "100nF 10%")
      (footprint "eagle-import:1608")
      (fields
        (field (name "PACKAGE") "1608")
        (field (name "SKU") "11-104A")
        (field (name "TEMP") "X7R")
        (field (name "VOLTAGE") "50V")
      )
      (libsource (lib "eagle-import") (part "CAP-H-1608-100NF"))
    )
    (comp (ref "C22")
      (value "100nF 10%")
      (footprint "eagle-import:1608")
      (fields
        (field (name "PACKAGE") "1608")
        (field (name "SKU") "11-104A")
        (field (name "TEMP") "X7R")
        (field (name "VOLTAGE") "50V")
      )
      (libsource (lib "eagle-import") (part "CAP-V-1608-100NF"))
    )
    (comp (ref "C23")
      (value "100nF 10%")
      (footprint "eagle-import:1608")
      (fields
        (field (name "PACKAGE") "1608")
        (field (name "SKU") "11-104A")
        (field (name "TEMP") "X7R")
        (field (name "VOLTAGE") "50V")
      )
      (libsource (lib "eagle-import") (part "CAP-V-1608-100NF"))
    )
    (comp (ref "C24")
      (value "100nF 10%")
      (footprint "eagle-import:1608")
      (fields
        (field (name "PACKAGE") "1608")
        (field (name "SKU") "11-104A")
        (field (name "TEMP") "X7R")
        (field (name "VOLTAGE") "50V")
      )
      (libsource (lib "eagle-import") (part "CAP-V-1608-100NF"))
    )
    (comp (ref "C29")
      (value "10µF 10%")
      (footprint "eagle-import:1608")
      (fields
        (field (name "PACKAGE") "1608")
        (field (name "SKU") "11-106A")
        (field (name "TEMP") "X5R")
        (field (name "VOLTAGE") "6.3V")
      )
      (libsource (lib "eagle-import") (part "CAP-V-1608-10UF"))
    )
    (comp (ref "C30")
      (value "100nF 10%")
      (footprint "eagle-import:1608")
      (fields
        (field (name "PACKAGE") "1608")
        (field (name "SKU") "11-104A")
        (field (name "TEMP") "X7R")
        (field (name "VOLTAGE") "50V")
      )
      (libsource (lib "eagle-import") (part "CAP-V-1608-100NF"))
    )
    (comp (ref "C31")
      (value "100nF 10%")
      (footprint "eagle-import:1608")
      (fields
        (field (name "PACKAGE") "1608")
        (field (name "SKU") "11-104A")
        (field (name "TEMP") "X7R")
        (field (name "VOLTAGE") "50V")
      )
      (libsource (lib "eagle-import") (part "CAP-V-1608-100NF"))
    )
    (comp (ref "C32")
      (value "C1206C226K8RACTU")
      (footprint "eagle-import:CAPC3216X110N")
      (fields (field (name "MF") "KEMET"))
      (libsource (lib "eagle-import") (part "C1206C226K8RACTU"))
    )
    (comp (ref "C33")
      (value "100nF 10%")
      (footprint "eagle-import:1608")
      (fields
        (field (name "PACKAGE") "1608")
        (field (name "SKU") "11-104A")
        (field (name "TEMP") "X7R")
        (field (name "VOLTAGE") "50V")
      )
      (libsource (lib "eagle-import") (part "CAP-V-1608-100NF"))
    )
    (comp (ref "D6")
      (value "SK6812")
      (footprint "eagle-import:LED_SK6812")
      (fields (field (name "MF") "Normand Electronics"))
      (libsource (lib "eagle-import") (part "SK6812"))
    )
    (comp (ref "D7")
      (value "SK6812")
      (footprint "eagle-import:LED_SK6812")
      (fields (field (name "MF") "Normand Electronics"))
      (libsource (lib "eagle-import") (part "SK6812"))
    )
    (comp (ref "D8")
      (value "SK6812")
      (footprint "eagle-import:LED_SK6812")
      (fields (field (name "MF") "Normand Electronics"))
      (libsource (lib "eagle-import") (part "SK6812"))
    )
    (comp (ref "JP1")
      (value "PINHD-1X11")
      (footprint "eagle-import:1X11")
      (libsource (lib "eagle-import") (part "PINHD-1X11"))
    )
    (comp (ref "JP2")
      (value "PINHD-1X16")
      (footprint "eagle-import:1X16")
      (libsource (lib "eagle-import") (part "PINHD-1X16"))
    )
    (comp (ref "Q8")
      (value "DMN53D0L")
      (footprint "eagle-import:SOT23-3")
      (fields
        (field (name "SKU") "56-0003")
        (field (name "VDS") "50V")
        (field (name "CURRENT") "500mA")
        (field (name "RDS") "4.5mΩ")
      )
      (libsource (lib "eagle-import") (part "MOSFET-N-SOT23-3"))
    )
    (comp (ref "R37")
      (value "10kΩ 0.1%")
      (footprint "eagle-import:1608")
      (fields
        (field (name "PACKAGE") "1608")
        (field (name "POWER") "1/8W")
        (field (name "SKU") "21-1002")
        (field (name "TEMP") "25ppm/°C")
      )
      (libsource (lib "eagle-import") (part "RES-V-1608-10K"))
    )
    (comp (ref "R38")
      (value "10kΩ 0.1%")
      (footprint "eagle-import:1608")
      (fields
        (field (name "PACKAGE") "1608")
        (field (name "POWER") "1/8W")
        (field (name "SKU") "21-1002")
        (field (name "TEMP") "25ppm/°C")
      )
      (libsource (lib "eagle-import") (part "RES-V-1608-10K"))
    )
    (comp (ref "R39")
      (value "10kΩ 0.1%")
      (footprint "eagle-import:1608")
      (fields
        (field (name "PACKAGE") "1608")
        (field (name "POWER") "1/8W")
        (field (name "SKU") "21-1002")
        (field (name "TEMP") "25ppm/°C")
      )
      (libsource (lib "eagle-import") (part "RES-V-1608-10K"))
    )
    (comp (ref "R40")
      (value "10kΩ 0.1%")
      (footprint "eagle-import:1608")
      (fields
        (field (name "PACKAGE") "1608")
        (field (name "POWER") "1/8W")
        (field (name "SKU") "21-1002")
        (field (name "TEMP") "25ppm/°C")
      )
      (libsource (lib "eagle-import") (part "RES-V-1608-10K"))
    )
    (comp (ref "R48")
      (value "10kΩ 0.1%")
      (footprint "eagle-import:1608")
      (fields
        (field (name "PACKAGE") "1608")
        (field (name "POWER") "1/8W")
        (field (name "SKU") "21-1002")
        (field (name "TEMP") "25ppm/°C")
      )
      (libsource (lib "eagle-import") (part "RES-V-1608-10K"))
    )
    (comp (ref "R49")
      (value "10kΩ 0.1%")
      (footprint "eagle-import:1608")
      (fields
        (field (name "PACKAGE") "1608")
        (field (name "POWER") "1/8W")
        (field (name "SKU") "21-1002")
        (field (name "TEMP") "25ppm/°C")
      )
      (libsource (lib "eagle-import") (part "RES-V-1608-10K"))
    )
    (comp (ref "SW6")
      (value "[Override]")
      (footprint "eagle-import:THT-6060")
      (fields (field (name "SKU") "49-0005"))
      (libsource (lib "eagle-import") (part "SWITCH-SPST-NO-THT-6060-B3F-1050"))
    )
    (comp (ref "TP12-3.3V")
      (value "TEST_POINT-SMD-C-1.25")
      (footprint "eagle-import:SMD-C-1.25")
      (libsource (lib "eagle-import") (part "TEST_POINT-SMD-C-1.25"))
    )
    (comp (ref "U$1")
      (value "LD1117AS33")
      (footprint "eagle-import:SOT223")
      (fields (field (name "MF") "STMicroelectronics"))
      (libsource (lib "eagle-import") (part "LD1117AS33"))
    )
    (comp (ref "U7")
      (value "ESP32-S2-MINI-1")
      (footprint "eagle-import:XCVR_ESP32-S2-MINI-1")
      (fields (field (name "MF") "Espressif Systems"))
      (libsource (lib "eagle-import") (part "ESP32-S2-MINI-1"))
    )
    (comp (ref "C1")
      (value "1µF 10%")
      (footprint "eagle-import:1608")
      (fields
        (field (name "PACKAGE") "1608")
        (field (name "SKU") "11-105A")
        (field (name "TEMP") "X5R")
        (field (name "VOLTAGE") "6.3V")
      )
      (libsource (lib "eagle-import") (part "CAP-V-1608-1UF"))
    )
    (comp (ref "C2")
      (value "1µF 10%")
      (footprint "eagle-import:1608")
      (fields
        (field (name "PACKAGE") "1608")
        (field (name "SKU") "11-105A")
        (field (name "TEMP") "X5R")
        (field (name "VOLTAGE") "6.3V")
      )
      (libsource (lib "eagle-import") (part "CAP-V-1608-1UF"))
    )
    (comp (ref "C3")
      (value "1µF 10%")
      (footprint "eagle-import:1608")
      (fields
        (field (name "PACKAGE") "1608")
        (field (name "SKU") "11-105A")
        (field (name "TEMP") "X5R")
        (field (name "VOLTAGE") "6.3V")
      )
      (libsource (lib "eagle-import") (part "CAP-V-1608-1UF"))
    )
    (comp (ref "C4")
      (value "100nF 10%")
      (footprint "eagle-import:1608")
      (fields
        (field (name "PACKAGE") "1608")
        (field (name "SKU") "11-104A")
        (field (name "TEMP") "X7R")
        (field (name "VOLTAGE") "50V")
      )
      (libsource (lib "eagle-import") (part "CAP-V-1608-100NF"))
    )
    (comp (ref "C5")
      (value "10µF 10%")
      (footprint "eagle-import:1608")
      (fields
        (field (name "PACKAGE") "1608")
        (field (name "SKU") "11-106A")
        (field (name "TEMP") "X5R")
        (field (name "VOLTAGE") "6.3V")
      )
      (libsource (lib "eagle-import") (part "CAP-V-1608-10UF"))
    )
    (comp (ref "C6")
      (value "100nF 10%")
      (footprint "eagle-import:1608")
      (fields
        (field (name "PACKAGE") "1608")
        (field (name "SKU") "11-104A")
        (field (name "TEMP") "X7R")
        (field (name "VOLTAGE") "50V")
      )
      (libsource (lib "eagle-import") (part "CAP-H-1608-100NF"))
    )
    (comp (ref "C7")
      (value "4.7µF 10%")
      (footprint "eagle-import:3216")
      (fields
        (field (name "PACKAGE") "3216")
        (field (name "SKU") "13-475A")
        (field (name "TEMP") "C0G")
        (field (name "VOLTAGE") "25V")
      )
      (libsource (lib "eagle-import") (part "CAP-V-3216-4.7UF"))
    )
    (comp (ref "C8")
      (value "22pF 5%")
      (footprint "eagle-import:1608")
      (fields
        (field (name "PACKAGE") "1608")
        (field (name "SKU") "11-220A")
        (field (name "TEMP") "C0G")
        (field (name "VOLTAGE") "50V")
      )
      (libsource (lib "eagle-import") (part "CAP-V-1608-22PF"))
    )
    (comp (ref "C18")
      (value "10µF 10%")
      (footprint "eagle-import:1608")
      (fields
        (field (name "PACKAGE") "1608")
        (field (name "SKU") "11-106A")
        (field (name "TEMP") "X5R")
        (field (name "VOLTAGE") "6.3V")
      )
      (libsource (lib "eagle-import") (part "CAP-V-1608-10UF"))
    )
    (comp (ref "C19")
      (value "1µF 10%")
      (footprint "eagle-import:1608")
      (fields
        (field (name "PACKAGE") "1608")
        (field (name "SKU") "11-105A")
        (field (name "TEMP") "X5R")
        (field (name "VOLTAGE") "6.3V")
      )
      (libsource (lib "eagle-import") (part "CAP-V-1608-1UF"))
    )
    (comp (ref "C20")
      (value "1µF 10%")
      (footprint "eagle-import:1608")
      (fields
        (field (name "PACKAGE") "1608")
        (field (name "SKU") "11-105A")
        (field (name "TEMP") "X5R")
        (field (name "VOLTAGE") "6.3V")
      )
      (libsource (lib "eagle-import") (part "CAP-V-1608-1UF"))
    )
    (comp (ref "D1")
      (value "LTC4411")
      (footprint "eagle-import:SOT23-5")
      (fields (field (name "SKU") "53-0001") (field (name "CURRENT") "2.6A"))
      (libsource (lib "eagle-import") (part "LTC4411"))
    )
    (comp (ref "D2")
      (value "MBRM120LT")
      (footprint "eagle-import:POWERMITE")
      (fields
        (field (name "SKU") "51-0002")
        (field (name "CURRENT") "1A")
        (field (name "VF") "F-0.45V")
        (field (name "VR") "R-20V")
      )
      (libsource (lib "eagle-import") (part "DIODE-SCHOTTKY-H-POWERMITE"))
    )
    (comp (ref "DS1")
      (value "Blue")
      (footprint "eagle-import:1608-POL")
      (fields
        (field (name "CURRENT") "20mA")
        (field (name "PACKAGE") "1608")
        (field (name "SKU") "63-0004")
        (field (name "VF") "3.3V")
      )
      (libsource (lib "eagle-import") (part "LED-V-1608-BLU"))
    )
    (comp (ref "DS2")
      (value "Green")
      (footprint "eagle-import:1608-POL")
      (fields
        (field (name "CURRENT") "20mA")
        (field (name "PACKAGE") "1608")
        (field (name "SKU") "63-0001")
        (field (name "VF") "2.2V")
      )
      (libsource (lib "eagle-import") (part "LED-V-1608-GRN"))
    )
    (comp (ref "J1")
      (value "USB4515-GF-A_REVA")
      (footprint "eagle-import:GCT_USB4515-GF-A_REVA")
      (fields (field (name "MF") "Global Connector Technology") (field (name "MP") "USB4515-GF-A"))
      (libsource (lib "eagle-import") (part "USB4515-GF-A_REVA"))
    )
    (comp (ref "L1")
      (value "10µH 20%")
      (footprint "eagle-import:6060")
      (fields
        (field (name "CURRENT") "1.8A")
        (field (name "DCR") "100mΩ")
        (field (name "PACKAGE") "6060")
        (field (name "SKU") "34-103A")
      )
      (libsource (lib "eagle-import") (part "INDUCTOR-H-6060-10UH"))
    )
    (comp (ref "Q1")
      (value "CSD16406Q3")
      (footprint "eagle-import:SON-3333")
      (fields
        (field (name "SKU") "56-0001")
        (field (name "VDS") "25V")
        (field (name "CURRENT") "19A")
        (field (name "RDS") "5.9mΩ")
      )
      (libsource (lib "eagle-import") (part "MOSFET-N-SON-3333"))
    )
    (comp (ref "Q2")
      (value "CSD16406Q3")
      (footprint "eagle-import:SON-3333")
      (fields
        (field (name "SKU") "56-0001")
        (field (name "VDS") "25V")
        (field (name "CURRENT") "19A")
        (field (name "RDS") "5.9mΩ")
      )
      (libsource (lib "eagle-import") (part "MOSFET-N-SON-3333"))
    )
    (comp (ref "R1")
      (value "10kΩ 0.1%")
      (footprint "eagle-import:1608")
      (fields
        (field (name "PACKAGE") "1608")
        (field (name "POWER") "1/8W")
        (field (name "SKU") "21-1002")
        (field (name "TEMP") "25ppm/°C")
      )
      (libsource (lib "eagle-import") (part "RES-V-1608-10K"))
    )
    (comp (ref "R2")
      (value "10kΩ 0.1%")
      (footprint "eagle-import:1608")
      (fields
        (field (name "PACKAGE") "1608")
        (field (name "POWER") "1/8W")
        (field (name "SKU") "21-1002")
        (field (name "TEMP") "25ppm/°C")
      )
      (libsource (lib "eagle-import") (part "RES-V-1608-10K"))
    )
    (comp (ref "R3")
      (value "10Ω 5%")
      (footprint "eagle-import:1608")
      (fields
        (field (name "PACKAGE") "1608")
        (field (name "POWER") "1/10W")
        (field (name "SKU") "21-10.0")
        (field (name "TEMP") "200ppm/°C")
      )
      (libsource (lib "eagle-import") (part "RES-V-1608-10R"))
    )
    (comp (ref "R4")
      (value "47kΩ 0.1%")
      (footprint "eagle-import:1608")
      (fields
        (field (name "PACKAGE") "1608")
        (field (name "POWER") "1/8W")
        (field (name "SKU") "21-4702")
        (field (name "TEMP") "25ppm/°C")
      )
      (libsource (lib "eagle-import") (part "RES-V-1608-47K"))
    )
    (comp (ref "R5")
      (value "20kΩ 0.5%")
      (footprint "eagle-import:1608")
      (fields
        (field (name "PACKAGE") "1608")
        (field (name "POWER") "1/5W")
        (field (name "SKU") "21-2002")
        (field (name "TEMP") "50ppm/°C")
      )
      (libsource (lib "eagle-import") (part "RES-V-1608-20K"))
    )
    (comp (ref "R18")
      (value "50mΩ 1%")
      (footprint "eagle-import:1608")
      (fields
        (field (name "PACKAGE") "1608")
        (field (name "POWER") "1/5W")
        (field (name "SKU") "21-0.05")
        (field (name "TEMP") "75ppm/°C")
      )
      (libsource (lib "eagle-import") (part "RES-H-1608-0.05R"))
    )
    (comp (ref "R19")
      (value "50mΩ 1%")
      (footprint "eagle-import:1608")
      (fields
        (field (name "PACKAGE") "1608")
        (field (name "POWER") "1/5W")
        (field (name "SKU") "21-0.05")
        (field (name "TEMP") "75ppm/°C")
      )
      (libsource (lib "eagle-import") (part "RES-H-1608-0.05R"))
    )
    (comp (ref "R20")
      (value "0Ω <20mΩ")
      (footprint "eagle-import:1608")
      (fields
        (field (name "PACKAGE") "1608")
        (field (name "POWER") "1/10W")
        (field (name "SKU") "21-0000")
        (field (name "TEMP") "70°C Max 2A")
      )
      (libsource (lib "eagle-import") (part "RES-V-1608-0"))
    )
    (comp (ref "R21")
      (value "0Ω <20mΩ")
      (footprint "eagle-import:1608")
      (fields
        (field (name "PACKAGE") "1608")
        (field (name "POWER") "1/10W")
        (field (name "SKU") "21-0000")
        (field (name "TEMP") "70°C Max 2A")
      )
      (libsource (lib "eagle-import") (part "RES-V-1608-0"))
    )
    (comp (ref "R22")
      (value "CRGH2010J2R0")
      (footprint "eagle-import:RESC5025X65N")
      (fields (field (name "COMMENT") "1879499-8") (field (name "MF") "TE Connectivity"))
      (libsource (lib "eagle-import") (part "CRGH2010J2R0"))
    )
    (comp (ref "R23")
      (value "10kΩ 0.1%")
      (footprint "eagle-import:1608")
      (fields
        (field (name "PACKAGE") "1608")
        (field (name "POWER") "1/8W")
        (field (name "SKU") "21-1002")
        (field (name "TEMP") "25ppm/°C")
      )
      (libsource (lib "eagle-import") (part "RES-V-1608-10K"))
    )
    (comp (ref "R24")
      (value "10kΩ 0.1%")
      (footprint "eagle-import:1608")
      (fields
        (field (name "PACKAGE") "1608")
        (field (name "POWER") "1/8W")
        (field (name "SKU") "21-1002")
        (field (name "TEMP") "25ppm/°C")
      )
      (libsource (lib "eagle-import") (part "RES-V-1608-10K"))
    )
    (comp (ref "R25")
      (value "442kΩ 1%")
      (footprint "eagle-import:1608")
      (fields
        (field (name "PACKAGE") "1608")
        (field (name "POWER") "1/10W")
        (field (name "SKU") "21-4423")
        (field (name "TEMP") "100ppm/°C")
      )
      (libsource (lib "eagle-import") (part "RES-V-1608-442K"))
    )
    (comp (ref "R26")
      (value "33kΩ 1%")
      (footprint "eagle-import:1608")
      (fields
        (field (name "PACKAGE") "1608")
        (field (name "POWER") "1/10W")
        (field (name "SKU") "21-3302")
        (field (name "TEMP") "100ppm/°C")
      )
      (libsource (lib "eagle-import") (part "RES-V-1608-33K"))
    )
    (comp (ref "R44")
      (value "75kΩ 0.1%")
      (footprint "eagle-import:1608")
      (fields
        (field (name "PACKAGE") "1608")
        (field (name "POWER") "1/10W")
        (field (name "SKU") "21-7502")
        (field (name "TEMP") "10ppm/°C")
      )
      (libsource (lib "eagle-import") (part "RES-V-1608-75K"))
    )
    (comp (ref "R45")
      (value "75kΩ 0.1%")
      (footprint "eagle-import:1608")
      (fields
        (field (name "PACKAGE") "1608")
        (field (name "POWER") "1/10W")
        (field (name "SKU") "21-7502")
        (field (name "TEMP") "10ppm/°C")
      )
      (libsource (lib "eagle-import") (part "RES-V-1608-75K"))
    )
    (comp (ref "R46")
      (value "100kΩ 0.1%")
      (footprint "eagle-import:1608")
      (fields
        (field (name "PACKAGE") "1608")
        (field (name "POWER") "1/8W")
        (field (name "SKU") "21-1003")
        (field (name "TEMP") "25ppm/°C")
      )
      (libsource (lib "eagle-import") (part "RES-V-1608-100K"))
    )
    (comp (ref "R47")
      (value "100kΩ 0.1%")
      (footprint "eagle-import:1608")
      (fields
        (field (name "PACKAGE") "1608")
        (field (name "POWER") "1/8W")
        (field (name "SKU") "21-1003")
        (field (name "TEMP") "25ppm/°C")
      )
      (libsource (lib "eagle-import") (part "RES-V-1608-100K"))
    )
    (comp (ref "SW1")
      (value "SWITCH-DPDT-100DP1T1B1M2QE")
      (footprint "eagle-import:100DP1T1B1M2QE")
      (fields (field (name "SKU") "49-0003"))
      (libsource (lib "eagle-import") (part "SWITCH-DPDT-100DP1T1B1M2QE"))
    )
    (comp (ref "SW2")
      (value "SWITCH-DPDT-100DP1T1B1M2QE")
      (footprint "eagle-import:100DP1T1B1M2QE")
      (fields (field (name "SKU") "49-0003"))
      (libsource (lib "eagle-import") (part "SWITCH-DPDT-100DP1T1B1M2QE"))
    )
    (comp (ref "TP1-5.0V")
      (value "TEST_POINT-SMD-C-1.25")
      (footprint "eagle-import:SMD-C-1.25")
      (libsource (lib "eagle-import") (part "TEST_POINT-SMD-C-1.25"))
    )
    (comp (ref "TP2-CHARGER")
      (value "TEST_POINT-SMD-C-1.25")
      (footprint "eagle-import:SMD-C-1.25")
      (libsource (lib "eagle-import") (part "TEST_POINT-SMD-C-1.25"))
    )
    (comp (ref "TP3-TS")
      (value "TEST_POINT-SMD-C-1.25")
      (footprint "eagle-import:SMD-C-1.25")
      (libsource (lib "eagle-import") (part "TEST_POINT-SMD-C-1.25"))
    )
    (comp (ref "TP14-D1_OUT")
      (value "TEST_POINT-SMD-C-1.25")
      (footprint "eagle-import:SMD-C-1.25")
      (libsource (lib "eagle-import") (part "TEST_POINT-SMD-C-1.25"))
    )
    (comp (ref "U1")
      (value "BQ24650")
      (footprint "eagle-import:QFN-16-3535")
      (fields (field (name "SKU") "60-0008"))
      (libsource (lib "eagle-import") (part "BQ24650"))
    )
  )
  (nets
    (net (code "1") (name "3.3V") (class "Default")
      (node (ref "C29") (pin "1") (pinfunction "1_1") (pintype "passive"))
      (node (ref "C31") (pin "1") (pinfunction "1_1") (pintype "passive"))
      (node (ref "C32") (pin "2") (pinfunction "2_2") (pintype "passive"))
      (node (ref "JP1") (pin "11") (pinfunction "11_11") (pintype "passive"))
      (node (ref "Q8") (pin "1") (pinfunction "G_1") (pintype "passive"))
      (node (ref "R25") (pin "2") (pinfunction "2_2") (pintype "passive"))
      (node (ref "R28") (pin "2") (pinfunction "2_2") (pintype "passive"))
      (node (ref "R30") (pin "2") (pinfunction "2_2") (pintype "passive"))
      (node (ref "R32") (pin "2") (pinfunction "2_2") (pintype "passive"))
      (node (ref "R37") (pin "2") (pinfunction "2_2") (pintype "passive"))
      (node (ref "R38") (pin "2") (pinfunction "2_2") (pintype "passive"))
      (node (ref "R39") (pin "2") (pinfunction "2_2") (pintype "passive"))
      (node (ref "R40") (pin "2") (pinfunction "2_2") (pintype "passive"))
      (node (ref "R48") (pin "2") (pinfunction "2_2") (pintype "passive"))
      (node (ref "TP12-3.3V") (pin "1") (pinfunction "1_1") (pintype "passive"))
      (node (ref "U$1") (pin "2") (pinfunction "V_OUT_2") (pintype "bidirectional"))
      (node (ref "U7") (pin "3") (pinfunction "3V3_3") (pintype "power_in"))
    )
    (net (code "2") (name "5.0V") (class "Default")
      (node (ref "C23") (pin "1") (pinfunction "1_1") (pintype "passive"))
      (node (ref "C24") (pin "1") (pinfunction "1_1") (pintype "passive"))
      (node (ref "C30") (pin "1") (pinfunction "1_1") (pintype "passive"))
      (node (ref "C33") (pin "1") (pinfunction "1_1") (pintype "passive"))
      (node (ref "D1") (pin "1") (pinfunction "IN_1") (pintype "passive"))
      (node (ref "D6") (pin "1") (pinfunction "VDD_1") (pintype "power_in"))
      (node (ref "D7") (pin "1") (pinfunction "VDD_1") (pintype "power_in"))
      (node (ref "D8") (pin "1") (pinfunction "VDD_1") (pintype "power_in"))
      (node (ref "J1") (pin "A9") (pinfunction "VBUS_A9") (pintype "power_in"))
      (node (ref "J1") (pin "B9") (pinfunction "VBUS_B9") (pintype "power_in"))
      (node (ref "JP1") (pin "1") (pinfunction "1_1") (pintype "passive"))
      (node (ref "R22") (pin "2") (pinfunction "2_2") (pintype "passive"))
      (node (ref "R23") (pin "2") (pinfunction "2_2") (pintype "passive"))
      (node (ref "R24") (pin "2") (pinfunction "2_2") (pintype "passive"))
      (node (ref "R49") (pin "2") (pinfunction "2_2") (pintype "passive"))
      (node (ref "SW1") (pin "1-A") (pinfunction "1-A_1-A") (pintype "passive"))
      (node (ref "SW1") (pin "1-B") (pinfunction "1-B_1-B") (pintype "passive"))
      (node (ref "SW3") (pin "1-A") (pinfunction "1-A_1-A") (pintype "passive"))
      (node (ref "SW3") (pin "1-B") (pinfunction "1-B_1-B") (pintype "passive"))
      (node (ref "SW4") (pin "1-A") (pinfunction "1-A_1-A") (pintype "passive"))
      (node (ref "SW4") (pin "1-B") (pinfunction "1-B_1-B") (pintype "passive"))
      (node (ref "SW5") (pin "1-A") (pinfunction "1-A_1-A") (pintype "passive"))
      (node (ref "SW5") (pin "1-B") (pinfunction "1-B_1-B") (pintype "passive"))
      (node (ref "TP1-5.0V") (pin "1") (pinfunction "1_1") (pintype "passive"))
      (node (ref "U$1") (pin "3") (pinfunction "V_IN_3") (pintype "bidirectional"))
    )
    (net (code "3") (name "CHARGER") (class "Default")
      (node (ref "C12") (pin "1") (pinfunction "1_1") (pintype "passive"))
      (node (ref "C13") (pin "1") (pinfunction "1_1") (pintype "passive"))
      (node (ref "C14") (pin "1") (pinfunction "1_1") (pintype "passive"))
      (node (ref "C18") (pin "1") (pinfunction "1_1") (pintype "passive"))
      (node (ref "C6") (pin "2") (pinfunction "2_2") (pintype "passive"))
      (node (ref "C7") (pin "1") (pinfunction "1_1") (pintype "passive"))
      (node (ref "C8") (pin "1") (pinfunction "1_1") (pintype "passive"))
      (node (ref "D3") (pin "1") (pinfunction "IN_1") (pintype "passive"))
      (node (ref "D4") (pin "1") (pinfunction "IN_1") (pintype "passive"))
      (node (ref "D5") (pin "1") (pinfunction "IN_1") (pintype "passive"))
      (node (ref "R1") (pin "2") (pinfunction "2_2") (pintype "passive"))
      (node (ref "R18") (pin "2") (pinfunction "2_2") (pintype "passive"))
      (node (ref "R19") (pin "2") (pinfunction "2_2") (pintype "passive"))
      (node (ref "TP2-CHARGER") (pin "1") (pinfunction "1_1") (pintype "passive"))
      (node (ref "U1") (pin "9") (pinfunction "SR_N_9") (pintype "input"))
    )
    (net (code "4") (name "CHASSIS") (class "Default")
      (node (ref "J1") (pin "S1") (pinfunction "SHIELD_S1") (pintype "power_in"))
      (node (ref "J1") (pin "S2") (pinfunction "SHIELD_S2") (pintype "power_in"))
      (node (ref "J1") (pin "S3") (pinfunction "SHIELD_S3") (pintype "power_in"))
      (node (ref "J1") (pin "S4") (pinfunction "SHIELD_S4") (pintype "power_in"))
      (node (ref "J3") (pin "S1") (pinfunction "SHIELD_S1") (pintype "power_in"))
      (node (ref "J3") (pin "S2") (pinfunction "SHIELD_S2") (pintype "power_in"))
      (node (ref "J3") (pin "S3") (pinfunction "SHIELD_S3") (pintype "power_in"))
      (node (ref "J3") (pin "S4") (pinfunction "SHIELD_S4") (pintype "power_in"))
      (node (ref "J3") (pin "S5") (pinfunction "SHIELD_S5") (pintype "power_in"))
      (node (ref "J3") (pin "S6") (pinfunction "SHIELD_S6") (pintype "power_in"))
      (node (ref "R43") (pin "1") (pinfunction "1_1") (pintype "passive"))
    )
    (net (code "5") (name "DGND") (class "Default")
      (node (ref "C25") (pin "2") (pinfunction "2_2") (pintype "passive"))
      (node (ref "C26") (pin "2") (pinfunction "2_2") (pintype "passive"))
      (node (ref "C27") (pin "2") (pinfunction "2_2") (pintype "passive"))
      (node (ref "C28") (pin "2") (pinfunction "2_2") (pintype "passive"))
      (node (ref "J3") (pin "5") (pinfunction "GND_5") (pintype "power_in"))
      (node (ref "R42") (pin "1") (pinfunction "1_1") (pintype "passive"))
      (node (ref "U5") (pin "29") (pinfunction "GND_29") (pintype "power_in"))
      (node (ref "U5") (pin "3") (pinfunction "GND_3") (pintype "power_in"))
    )
    (net (code "6") (name "LEDS") (class "Default")
      (node (ref "Q8") (pin "2") (pinfunction "S_2") (pintype "passive"))
      (node (ref "R48") (pin "1") (pinfunction "1_1") (pintype "passive"))
      (node (ref "U7") (pin "15") (pinfunction "IO11_15") (pintype "bidirectional"))
    )
    (net (code "7") (name "Net-(C19-Pad1)") (class "Default")
      (node (ref "C19") (pin "1") (pinfunction "1_1") (pintype "passive"))
      (node (ref "C20") (pin "1") (pinfunction "1_1") (pintype "passive"))
      (node (ref "R22") (pin "1") (pinfunction "1_1") (pintype "passive"))
    )
    (net (code "8") (name "Net-(D1-OUT)") (class "Default")
      (node (ref "C5") (pin "1") (pinfunction "1_1") (pintype "passive"))
      (node (ref "D1") (pin "5") (pinfunction "OUT_5") (pintype "passive"))
      (node (ref "Q1") (pin "5") (pinfunction "D_5") (pintype "passive"))
      (node (ref "Q1") (pin "6") (pinfunction "D_6") (pintype "passive"))
      (node (ref "Q1") (pin "7") (pinfunction "D_7") (pintype "passive"))
      (node (ref "Q1") (pin "8") (pinfunction "D_8") (pintype "passive"))
      (node (ref "Q1") (pin "PAD") (pinfunction "D_PAD") (pintype "passive"))
      (node (ref "R3") (pin "2") (pinfunction "2_2") (pintype "passive"))
      (node (ref "R4") (pin "2") (pinfunction "2_2") (pintype "passive"))
      (node (ref "TP14-D1_OUT") (pin "1") (pinfunction "1_1") (pintype "passive"))
    )
    (net (code "9") (name "Net-(D3-OUT)") (class "Default")
      (node (ref "BT1") (pin "C") (pinfunction "C_C") (pintype "passive"))
      (node (ref "C15") (pin "1") (pinfunction "1_1") (pintype "passive"))
      (node (ref "D3") (pin "5") (pinfunction "OUT_5") (pintype "passive"))
      (node (ref "R6") (pin "2") (pinfunction "2_2") (pintype "passive"))
      (node (ref "TP4-BATT_A") (pin "1") (pinfunction "1_1") (pintype "passive"))
    )
    (net (code "10") (name "Net-(D4-OUT)") (class "Default")
      (node (ref "BT2") (pin "C") (pinfunction "C_C") (pintype "passive"))
      (node (ref "C16") (pin "1") (pinfunction "1_1") (pintype "passive"))
      (node (ref "D4") (pin "5") (pinfunction "OUT_5") (pintype "passive"))
      (node (ref "R10") (pin "2") (pinfunction "2_2") (pintype "passive"))
      (node (ref "TP5-BATT_B") (pin "1") (pinfunction "1_1") (pintype "passive"))
    )
    (net (code "11") (name "Net-(D5-OUT)") (class "Default")
      (node (ref "BT3") (pin "C") (pinfunction "C_C") (pintype "passive"))
      (node (ref "C17") (pin "1") (pinfunction "1_1") (pintype "passive"))
      (node (ref "D5") (pin "5") (pinfunction "OUT_5") (pintype "passive"))
      (node (ref "R14") (pin "2") (pinfunction "2_2") (pintype "passive"))
      (node (ref "TP6-BATT_C") (pin "1") (pinfunction "1_1") (pintype "passive"))
    )
    (net (code "12") (name "Net-(D6-DIN)") (class "Default")
      (node (ref "D6") (pin "4") (pinfunction "DIN_4") (pintype "input"))
      (node (ref "Q8") (pin "3") (pinfunction "D_3") (pintype "passive"))
      (node (ref "R49") (pin "1") (pinfunction "1_1") (pintype "passive"))
    )
    (net (code "13") (name "Net-(D6-DOUT)") (class "Default")
      (node (ref "D6") (pin "2") (pinfunction "DOUT_2") (pintype "output"))
      (node (ref "D7") (pin "4") (pinfunction "DIN_4") (pintype "input"))
    )
    (net (code "14") (name "Net-(D7-DOUT)") (class "Default")
      (node (ref "D7") (pin "2") (pinfunction "DOUT_2") (pintype "output"))
      (node (ref "D8") (pin "4") (pinfunction "DIN_4") (pintype "input"))
    )
    (net (code "15") (name "Net-(DS1-PadA)") (class "Default")
      (node (ref "DS1") (pin "A") (pinfunction "A_A") (pintype "passive"))
      (node (ref "R23") (pin "1") (pinfunction "1_1") (pintype "passive"))
    )
    (net (code "16") (name "Net-(DS2-PadA)") (class "Default")
      (node (ref "DS2") (pin "A") (pinfunction "A_A") (pintype "passive"))
      (node (ref "R24") (pin "1") (pinfunction "1_1") (pintype "passive"))
    )
    (net (code "17") (name "Net-(DS3-PadA)") (class "Default")
      (node (ref "DS3") (pin "A") (pinfunction "A_A") (pintype "passive"))
      (node (ref "R35") (pin "1") (pinfunction "1_1") (pintype "passive"))
    )
    (net (code "18") (name "Net-(DS4-PadA)") (class "Default")
      (node (ref "DS4") (pin "A") (pinfunction "A_A") (pintype "passive"))
      (node (ref "R36") (pin "1") (pinfunction "1_1") (pintype "passive"))
    )
    (net (code "19") (name "Net-(J3-D+)") (class "Default")
      (node (ref "J3") (pin "3") (pinfunction "D+_3") (pintype "bidirectional"))
      (node (ref "U5") (pin "4") (pinfunction "D+_4") (pintype "bidirectional"))
    )
    (net (code "20") (name "Net-(J3-D-)") (class "Default")
      (node (ref "J3") (pin "2") (pinfunction "D-_2") (pintype "bidirectional"))
      (node (ref "U5") (pin "5") (pinfunction "D-_5") (pintype "bidirectional"))
    )
    (net (code "21") (name "Net-(J3-VDD)") (class "Default")
      (node (ref "C25") (pin "1") (pinfunction "1_1") (pintype "passive"))
      (node (ref "C27") (pin "1") (pinfunction "1_1") (pintype "passive"))
      (node (ref "J3") (pin "1") (pinfunction "VDD_1") (pintype "power_in"))
      (node (ref "R35") (pin "2") (pinfunction "2_2") (pintype "passive"))
      (node (ref "R36") (pin "2") (pinfunction "2_2") (pintype "passive"))
      (node (ref "TP10-USB_5.0V") (pin "1") (pinfunction "1_1") (pintype "passive"))
      (node (ref "U5") (pin "7") (pinfunction "VREGIN_7") (pintype "input"))
      (node (ref "U5") (pin "8") (pinfunction "VBUS_8") (pintype "input"))
    )
    (net (code "22") (name "Net-(Q1-G)") (class "Default")
      (node (ref "Q1") (pin "4") (pinfunction "G_4") (pintype "passive"))
      (node (ref "U1") (pin "15") (pinfunction "HIGHDV_15") (pintype "output"))
    )
    (net (code "23") (name "Net-(Q2-G)") (class "Default")
      (node (ref "Q2") (pin "4") (pinfunction "G_4") (pintype "passive"))
      (node (ref "U1") (pin "13") (pinfunction "LODRV_13") (pintype "output"))
    )
    (net (code "24") (name "Net-(Q3-G1)") (class "Default")
      (node (ref "Q3") (pin "3") (pinfunction "G1_3") (pintype "passive"))
      (node (ref "R8") (pin "2") (pinfunction "2_2") (pintype "passive"))
      (node (ref "U2") (pin "2") (pinfunction "COUT_2") (pintype "output"))
    )
    (net (code "25") (name "Net-(Q3-G2)") (class "Default")
      (node (ref "Q3") (pin "4") (pinfunction "G2_4") (pintype "passive"))
      (node (ref "R7") (pin "2") (pinfunction "2_2") (pintype "passive"))
      (node (ref "U2") (pin "3") (pinfunction "DOUT_3") (pintype "output"))
    )
    (net (code "26") (name "Net-(Q3-S2)") (class "Default")
      (node (ref "BT1") (pin "A") (pinfunction "A_A") (pintype "passive"))
      (node (ref "C9") (pin "2") (pinfunction "2_2") (pintype "passive"))
      (node (ref "Q3") (pin "6") (pinfunction "S2_6") (pintype "passive"))
      (node (ref "R7") (pin "1") (pinfunction "1_1") (pintype "passive"))
      (node (ref "U2") (pin "4") (pinfunction "VSS_4") (pintype "power_in"))
    )
    (net (code "27") (name "Net-(Q4-G1)") (class "Default")
      (node (ref "Q4") (pin "3") (pinfunction "G1_3") (pintype "passive"))
      (node (ref "R12") (pin "2") (pinfunction "2_2") (pintype "passive"))
      (node (ref "U3") (pin "2") (pinfunction "COUT_2") (pintype "output"))
    )
    (net (code "28") (name "Net-(Q4-G2)") (class "Default")
      (node (ref "Q4") (pin "4") (pinfunction "G2_4") (pintype "passive"))
      (node (ref "R11") (pin "2") (pinfunction "2_2") (pintype "passive"))
      (node (ref "U3") (pin "3") (pinfunction "DOUT_3") (pintype "output"))
    )
    (net (code "29") (name "Net-(Q4-S2)") (class "Default")
      (node (ref "BT2") (pin "A") (pinfunction "A_A") (pintype "passive"))
      (node (ref "C10") (pin "2") (pinfunction "2_2") (pintype "passive"))
      (node (ref "Q4") (pin "6") (pinfunction "S2_6") (pintype "passive"))
      (node (ref "R11") (pin "1") (pinfunction "1_1") (pintype "passive"))
      (node (ref "U3") (pin "4") (pinfunction "VSS_4") (pintype "power_in"))
    )
    (net (code "30") (name "Net-(Q5-G1)") (class "Default")
      (node (ref "Q5") (pin "3") (pinfunction "G1_3") (pintype "passive"))
      (node (ref "R16") (pin "2") (pinfunction "2_2") (pintype "passive"))
      (node (ref "U4") (pin "2") (pinfunction "COUT_2") (pintype "output"))
    )
    (net (code "31") (name "Net-(Q5-G2)") (class "Default")
      (node (ref "Q5") (pin "4") (pinfunction "G2_4") (pintype "passive"))
      (node (ref "R15") (pin "2") (pinfunction "2_2") (pintype "passive"))
      (node (ref "U4") (pin "3") (pinfunction "DOUT_3") (pintype "output"))
    )
    (net (code "32") (name "Net-(Q5-S2)") (class "Default")
      (node (ref "BT3") (pin "A") (pinfunction "A_A") (pintype "passive"))
      (node (ref "C11") (pin "2") (pinfunction "2_2") (pintype "passive"))
      (node (ref "Q5") (pin "6") (pinfunction "S2_6") (pintype "passive"))
      (node (ref "R15") (pin "1") (pinfunction "1_1") (pintype "passive"))
      (node (ref "U4") (pin "4") (pinfunction "VSS_4") (pintype "power_in"))
    )
    (net (code "33") (name "Net-(Q6-B)") (class "Default")
      (node (ref "Q6") (pin "1") (pinfunction "B_1") (pintype "passive"))
      (node (ref "R33") (pin "2") (pinfunction "2_2") (pintype "passive"))
    )
    (net (code "34") (name "Net-(Q6-E)") (class "Default")
      (node (ref "Q6") (pin "2") (pinfunction "E_2") (pintype "passive"))
      (node (ref "R34") (pin "1") (pinfunction "1_1") (pintype "passive"))
      (node (ref "U5") (pin "24") (pinfunction "RTS_24") (pintype "output"))
    )
    (net (code "35") (name "Net-(Q7-B)") (class "Default")
      (node (ref "Q7") (pin "1") (pinfunction "B_1") (pintype "passive"))
      (node (ref "R34") (pin "2") (pinfunction "2_2") (pintype "passive"))
    )
    (net (code "36") (name "Net-(Q7-E)") (class "Default")
      (node (ref "Q7") (pin "2") (pinfunction "E_2") (pintype "passive"))
      (node (ref "R33") (pin "1") (pinfunction "1_1") (pintype "passive"))
      (node (ref "U5") (pin "28") (pinfunction "DTR_28") (pintype "output"))
    )
    (net (code "37") (name "Net-(R1-Pad1)") (class "Default")
      (node (ref "R1") (pin "1") (pinfunction "1_1") (pintype "passive"))
      (node (ref "R20") (pin "2") (pinfunction "2_2") (pintype "passive"))
    )
    (net (code "38") (name "Net-(R2-Pad2)") (class "Default")
      (node (ref "R2") (pin "2") (pinfunction "2_2") (pintype "passive"))
      (node (ref "R21") (pin "1") (pinfunction "1_1") (pintype "passive"))
    )
    (net (code "39") (name "Net-(R25-Pad1)") (class "Default")
      (node (ref "R25") (pin "1") (pinfunction "1_1") (pintype "passive"))
      (node (ref "R26") (pin "2") (pinfunction "2_2") (pintype "passive"))
    )
    (net (code "40") (name "Net-(R27-Pad2)") (class "Default")
      (node (ref "R27") (pin "2") (pinfunction "2_2") (pintype "passive"))
      (node (ref "R28") (pin "1") (pinfunction "1_1") (pintype "passive"))
    )
    (net (code "41") (name "Net-(R29-Pad2)") (class "Default")
      (node (ref "R29") (pin "2") (pinfunction "2_2") (pintype "passive"))
      (node (ref "R30") (pin "1") (pinfunction "1_1") (pintype "passive"))
    )
    (net (code "42") (name "Net-(R31-Pad2)") (class "Default")
      (node (ref "R31") (pin "2") (pinfunction "2_2") (pintype "passive"))
      (node (ref "R32") (pin "1") (pinfunction "1_1") (pintype "passive"))
    )
    (net (code "43") (name "Net-(U1-BTST)") (class "Default")
      (node (ref "C4") (pin "1") (pinfunction "1_1") (pintype "passive"))
      (node (ref "D2") (pin "C") (pinfunction "C_C") (pintype "passive"))
      (node (ref "U1") (pin "16") (pinfunction "BTST_16") (pintype "power_in"))
    )
    (net (code "44") (name "Net-(U1-PH)") (class "Default")
      (node (ref "C4") (pin "2") (pinfunction "2_2") (pintype "passive"))
      (node (ref "L1") (pin "1") (pinfunction "1_1") (pintype "passive"))
      (node (ref "Q1") (pin "1") (pinfunction "S_1") (pintype "passive"))
      (node (ref "Q1") (pin "2") (pinfunction "S_2") (pintype "passive"))
      (node (ref "Q1") (pin "3") (pinfunction "S_3") (pintype "passive"))
      (node (ref "Q2") (pin "5") (pinfunction "D_5") (pintype "passive"))
      (node (ref "Q2") (pin "6") (pinfunction "D_6") (pintype "passive"))
      (node (ref "Q2") (pin "7") (pinfunction "D_7") (pintype "passive"))
      (node (ref "Q2") (pin "8") (pinfunction "D_8") (pintype "passive"))
      (node (ref "Q2") (pin "PAD") (pinfunction "D_PAD") (pintype "passive"))
      (node (ref "U1") (pin "14") (pinfunction "PH_14") (pintype "power_in"))
    )
    (net (code "45") (name "Net-(U1-REGN)") (class "Default")
      (node (ref "C3") (pin "1") (pinfunction "1_1") (pintype "passive"))
      (node (ref "D2") (pin "A") (pinfunction "A_A") (pintype "passive"))
      (node (ref "U1") (pin "12") (pinfunction "REGN_12") (pintype "power_in"))
    )
    (net (code "46") (name "Net-(U1-SR_P)") (class "Default")
      (node (ref "C6") (pin "1") (pinfunction "1_1") (pintype "passive"))
      (node (ref "L1") (pin "2") (pinfunction "2_2") (pintype "passive"))
      (node (ref "R18") (pin "1") (pinfunction "1_1") (pintype "passive"))
      (node (ref "R19") (pin "1") (pinfunction "1_1") (pintype "passive"))
      (node (ref "U1") (pin "10") (pinfunction "SR_P_10") (pintype "input"))
    )
    (net (code "47") (name "Net-(U1-STAT1)") (class "Default")
      (node (ref "DS1") (pin "C") (pinfunction "C_C") (pintype "passive"))
      (node (ref "R44") (pin "2") (pinfunction "2_2") (pintype "passive"))
      (node (ref "U1") (pin "3") (pinfunction "STAT1_3") (pintype "output"))
    )
    (net (code "48") (name "Net-(U1-STAT2)") (class "Default")
      (node (ref "DS2") (pin "C") (pinfunction "C_C") (pintype "passive"))
      (node (ref "R45") (pin "2") (pinfunction "2_2") (pintype "passive"))
      (node (ref "U1") (pin "5") (pinfunction "STAT2_5") (pintype "output"))
    )
    (net (code "49") (name "Net-(U1-THERM_EN)") (class "Default")
      (node (ref "C2") (pin "1") (pinfunction "1_1") (pintype "passive"))
      (node (ref "U1") (pin "6") (pinfunction "VREF_6") (pintype "input"))
      (node (ref "U1") (pin "7") (pinfunction "THERM_EN_7") (pintype "output"))
    )
    (net (code "50") (name "Net-(U1-VCC)") (class "Default")
      (node (ref "C1") (pin "1") (pinfunction "1_1") (pintype "passive"))
      (node (ref "R3") (pin "1") (pinfunction "1_1") (pintype "passive"))
      (node (ref "U1") (pin "1") (pinfunction "VCC_1") (pintype "power_in"))
    )
    (net (code "51") (name "Net-(U1-VFB)") (class "Default")
      (node (ref "C8") (pin "2") (pinfunction "2_2") (pintype "passive"))
      (node (ref "R20") (pin "1") (pinfunction "1_1") (pintype "passive"))
      (node (ref "R21") (pin "2") (pinfunction "2_2") (pintype "passive"))
      (node (ref "U1") (pin "8") (pinfunction "VFB_8") (pintype "input"))
    )
    (net (code "52") (name "Net-(U2-BAT)") (class "Default")
      (node (ref "C9") (pin "1") (pinfunction "1_1") (pintype "passive"))
      (node (ref "R6") (pin "1") (pinfunction "1_1") (pintype "passive"))
      (node (ref "U2") (pin "5") (pinfunction "BAT_5") (pintype "power_in"))
    )
    (net (code "53") (name "Net-(U2-V-)") (class "Default")
      (node (ref "R9") (pin "2") (pinfunction "2_2") (pintype "passive"))
      (node (ref "U2") (pin "6") (pinfunction "V-_6") (pintype "input"))
    )
    (net (code "54") (name "Net-(U3-BAT)") (class "Default")
      (node (ref "C10") (pin "1") (pinfunction "1_1") (pintype "passive"))
      (node (ref "R10") (pin "1") (pinfunction "1_1") (pintype "passive"))
      (node (ref "U3") (pin "5") (pinfunction "BAT_5") (pintype "power_in"))
    )
    (net (code "55") (name "Net-(U3-V-)") (class "Default")
      (node (ref "R13") (pin "2") (pinfunction "2_2") (pintype "passive"))
      (node (ref "U3") (pin "6") (pinfunction "V-_6") (pintype "input"))
    )
    (net (code "56") (name "Net-(U4-BAT)") (class "Default")
      (node (ref "C11") (pin "1") (pinfunction "1_1") (pintype "passive"))
      (node (ref "R14") (pin "1") (pinfunction "1_1") (pintype "passive"))
      (node (ref "U4") (pin "5") (pinfunction "BAT_5") (pintype "power_in"))
    )
    (net (code "57") (name "Net-(U4-V-)") (class "Default")
      (node (ref "R17") (pin "2") (pinfunction "2_2") (pintype "passive"))
      (node (ref "U4") (pin "6") (pinfunction "V-_6") (pintype "input"))
    )
    (net (code "58") (name "Net-(U5-GPIO.0{slash}TXT)") (class "Default")
      (node (ref "DS3") (pin "C") (pinfunction "C_C") (pintype "passive"))
      (node (ref "U5") (pin "19") (pinfunction "GPIO.0/TXT_19") (pintype "bidirectional"))
    )
    (net (code "59") (name "Net-(U5-GPIO.1{slash}RXT)") (class "Default")
      (node (ref "DS4") (pin "C") (pinfunction "C_C") (pintype "passive"))
      (node (ref "U5") (pin "18") (pinfunction "GPIO.1/RXT_18") (pintype "bidirectional"))
    )
    (net (code "60") (name "Net-(U5-VDD)") (class "Default")
      (node (ref "C26") (pin "1") (pinfunction "1_1") (pintype "passive"))
      (node (ref "C28") (pin "1") (pinfunction "1_1") (pintype "passive"))
      (node (ref "TP11-CP2102N_VDD") (pin "1") (pinfunction "1_1") (pintype "passive"))
      (node (ref "U5") (pin "6") (pinfunction "VDD_6") (pintype "power_in"))
    )
    (net (code "61") (name "Net-(U7-IO12)") (class "Default")
      (node (ref "JP1") (pin "9") (pinfunction "9_9") (pintype "passive"))
      (node (ref "U7") (pin "16") (pinfunction "IO12_16") (pintype "bidirectional"))
    )
    (net (code "62") (name "Net-(U7-IO13)") (class "Default")
      (node (ref "JP1") (pin "8") (pinfunction "8_8") (pintype "passive"))
      (node (ref "U7") (pin "17") (pinfunction "IO13_17") (pintype "bidirectional"))
    )
    (net (code "63") (name "Net-(U7-IO14)") (class "Default")
      (node (ref "JP1") (pin "7") (pinfunction "7_7") (pintype "passive"))
      (node (ref "U7") (pin "18") (pinfunction "IO14_18") (pintype "bidirectional"))
    )
    (net (code "64") (name "Net-(U7-IO15)") (class "Default")
      (node (ref "JP1") (pin "6") (pinfunction "6_6") (pintype "passive"))
      (node (ref "U7") (pin "19") (pinfunction "IO15_19") (pintype "bidirectional"))
    )
    (net (code "65") (name "Net-(U7-IO16)") (class "Default")
      (node (ref "JP1") (pin "5") (pinfunction "5_5") (pintype "passive"))
      (node (ref "U7") (pin "20") (pinfunction "IO16_20") (pintype "bidirectional"))
    )
    (net (code "66") (name "Net-(U7-IO17)") (class "Default")
      (node (ref "JP1") (pin "4") (pinfunction "4_4") (pintype "passive"))
      (node (ref "U7") (pin "21") (pinfunction "IO17_21") (pintype "bidirectional"))
    )
    (net (code "67") (name "Net-(U7-IO18)") (class "Default")
      (node (ref "JP1") (pin "3") (pinfunction "3_3") (pintype "passive"))
      (node (ref "U7") (pin "22") (pinfunction "IO18_22") (pintype "bidirectional"))
    )
    (net (code "68") (name "Net-(U7-IO19)") (class "Default")
      (node (ref "JP2") (pin "1") (pinfunction "1_1") (pintype "passive"))
      (node (ref "U7") (pin "23") (pinfunction "IO19_23") (pintype "bidirectional"))
    )
    (net (code "69") (name "Net-(U7-IO20)") (class "Default")
      (node (ref "JP2") (pin "2") (pinfunction "2_2") (pintype "passive"))
      (node (ref "U7") (pin "24") (pinfunction "IO20_24") (pintype "bidirectional"))
    )
    (net (code "70") (name "Net-(U7-IO21)") (class "Default")
      (node (ref "JP2") (pin "3") (pinfunction "3_3") (pintype "passive"))
      (node (ref "U7") (pin "25") (pinfunction "IO21_25") (pintype "bidirectional"))
    )
    (net (code "71") (name "Net-(U7-IO26)") (class "Default")
      (node (ref "JP2") (pin "4") (pinfunction "4_4") (pintype "passive"))
      (node (ref "U7") (pin "26") (pinfunction "IO26_26") (pintype "bidirectional"))
    )
    (net (code "72") (name "Net-(U7-IO33)") (class "Default")
      (node (ref "JP2") (pin "5") (pinfunction "5_5") (pintype "passive"))
      (node (ref "U7") (pin "28") (pinfunction "IO33_28") (pintype "bidirectional"))
    )
    (net (code "73") (name "Net-(U7-IO34)") (class "Default")
      (node (ref "JP2") (pin "6") (pinfunction "6_6") (pintype "passive"))
      (node (ref "U7") (pin "29") (pinfunction "IO34_29") (pintype "bidirectional"))
    )
    (net (code "74") (name "Net-(U7-IO35)") (class "Default")
      (node (ref "JP2") (pin "7") (pinfunction "7_7") (pintype "passive"))
      (node (ref "U7") (pin "31") (pinfunction "IO35_31") (pintype "bidirectional"))
    )
    (net (code "75") (name "Net-(U7-IO36)") (class "Default")
      (node (ref "JP2") (pin "8") (pinfunction "8_8") (pintype "passive"))
      (node (ref "U7") (pin "32") (pinfunction "IO36_32") (pintype "bidirectional"))
    )
    (net (code "76") (name "Net-(U7-IO37)") (class "Default")
      (node (ref "JP2") (pin "9") (pinfunction "9_9") (pintype "passive"))
      (node (ref "U7") (pin "33") (pinfunction "IO37_33") (pintype "bidirectional"))
    )
    (net (code "77") (name "Net-(U7-IO38)") (class "Default")
      (node (ref "JP2") (pin "10") (pinfunction "10_10") (pintype "passive"))
      (node (ref "U7") (pin "34") (pinfunction "IO38_34") (pintype "bidirectional"))
    )
    (net (code "78") (name "Net-(U7-IO39)") (class "Default")
      (node (ref "JP2") (pin "11") (pinfunction "11_11") (pintype "passive"))
      (node (ref "U7") (pin "35") (pinfunction "IO39_35") (pintype "bidirectional"))
    )
    (net (code "79") (name "Net-(U7-IO40)") (class "Default")
      (node (ref "JP2") (pin "12") (pinfunction "12_12") (pintype "passive"))
      (node (ref "U7") (pin "36") (pinfunction "IO40_36") (pintype "bidirectional"))
    )
    (net (code "80") (name "Net-(U7-IO41)") (class "Default")
      (node (ref "JP2") (pin "13") (pinfunction "13_13") (pintype "passive"))
      (node (ref "U7") (pin "37") (pinfunction "IO41_37") (pintype "bidirectional"))
    )
    (net (code "81") (name "Net-(U7-IO42)") (class "Default")
      (node (ref "JP2") (pin "14") (pinfunction "14_14") (pintype "passive"))
      (node (ref "U7") (pin "38") (pinfunction "IO42_38") (pintype "bidirectional"))
    )
    (net (code "82") (name "Net-(U7-IO45)") (class "Default")
      (node (ref "JP2") (pin "15") (pinfunction "15_15") (pintype "passive"))
      (node (ref "U7") (pin "41") (pinfunction "IO45_41") (pintype "bidirectional"))
    )
    (net (code "83") (name "Net-(U7-IO46)") (class "Default")
      (node (ref "JP2") (pin "16") (pinfunction "16_16") (pintype "passive"))
      (node (ref "U7") (pin "44") (pinfunction "IO46_44") (pintype "input"))
    )
    (net (code "84") (name "PGND") (class "Default")
      (node (ref "C1") (pin "2") (pinfunction "2_2") (pintype "passive"))
      (node (ref "C12") (pin "2") (pinfunction "2_2") (pintype "passive"))
      (node (ref "C13") (pin "2") (pinfunction "2_2") (pintype "passive"))
      (node (ref "C14") (pin "2") (pinfunction "2_2") (pintype "passive"))
      (node (ref "C15") (pin "2") (pinfunction "2_2") (pintype "passive"))
      (node (ref "C16") (pin "2") (pinfunction "2_2") (pintype "passive"))
      (node (ref "C17") (pin "2") (pinfunction "2_2") (pintype "passive"))
      (node (ref "C18") (pin "2") (pinfunction "2_2") (pintype "passive"))
      (node (ref "C19") (pin "2") (pinfunction "2_2") (pintype "passive"))
      (node (ref "C2") (pin "2") (pinfunction "2_2") (pintype "passive"))
      (node (ref "C20") (pin "2") (pinfunction "2_2") (pintype "passive"))
      (node (ref "C21") (pin "1") (pinfunction "1_1") (pintype "passive"))
      (node (ref "C22") (pin "2") (pinfunction "2_2") (pintype "passive"))
      (node (ref "C23") (pin "2") (pinfunction "2_2") (pintype "passive"))
      (node (ref "C24") (pin "2") (pinfunction "2_2") (pintype "passive"))
      (node (ref "C29") (pin "2") (pinfunction "2_2") (pintype "passive"))
      (node (ref "C3") (pin "2") (pinfunction "2_2") (pintype "passive"))
      (node (ref "C30") (pin "2") (pinfunction "2_2") (pintype "passive"))
      (node (ref "C31") (pin "2") (pinfunction "2_2") (pintype "passive"))
      (node (ref "C32") (pin "1") (pinfunction "1_1") (pintype "passive"))
      (node (ref "C33") (pin "2") (pinfunction "2_2") (pintype "passive"))
      (node (ref "C5") (pin "2") (pinfunction "2_2") (pintype "passive"))
      (node (ref "C7") (pin "2") (pinfunction "2_2") (pintype "passive"))
      (node (ref "D1") (pin "2") (pinfunction "GND_2") (pintype "power_in"))
      (node (ref "D3") (pin "2") (pinfunction "GND_2") (pintype "power_in"))
      (node (ref "D4") (pin "2") (pinfunction "GND_2") (pintype "power_in"))
      (node (ref "D5") (pin "2") (pinfunction "GND_2") (pintype "power_in"))
      (node (ref "D6") (pin "3") (pinfunction "VSS_3") (pintype "power_in"))
      (node (ref "D7") (pin "3") (pinfunction "VSS_3") (pintype "power_in"))
      (node (ref "D8") (pin "3") (pinfunction "VSS_3") (pintype "power_in"))
      (node (ref "J1") (pin "A12") (pinfunction "GND_A12") (pintype "power_in"))
      (node (ref "J1") (pin "B12") (pinfunction "GND_B12") (pintype "power_in"))
      (node (ref "JP1") (pin "10") (pinfunction "10_10") (pintype "passive"))
      (node (ref "JP1") (pin "2") (pinfunction "2_2") (pintype "passive"))
      (node (ref "Q2") (pin "1") (pinfunction "S_1") (pintype "passive"))
      (node (ref "Q2") (pin "2") (pinfunction "S_2") (pintype "passive"))
      (node (ref "Q2") (pin "3") (pinfunction "S_3") (pintype "passive"))
      (node (ref "Q3") (pin "1") (pinfunction "S1_1") (pintype "passive"))
      (node (ref "Q4") (pin "1") (pinfunction "S1_1") (pintype "passive"))
      (node (ref "Q5") (pin "1") (pinfunction "S1_1") (pintype "passive"))
      (node (ref "R12") (pin "1") (pinfunction "1_1") (pintype "passive"))
      (node (ref "R13") (pin "1") (pinfunction "1_1") (pintype "passive"))
      (node (ref "R16") (pin "1") (pinfunction "1_1") (pintype "passive"))
      (node (ref "R17") (pin "1") (pinfunction "1_1") (pintype "passive"))
      (node (ref "R2") (pin "1") (pinfunction "1_1") (pintype "passive"))
      (node (ref "R42") (pin "2") (pinfunction "2_2") (pintype "passive"))
      (node (ref "R43") (pin "2") (pinfunction "2_2") (pintype "passive"))
      (node (ref "R46") (pin "1") (pinfunction "1_1") (pintype "passive"))
      (node (ref "R47") (pin "1") (pinfunction "1_1") (pintype "passive"))
      (node (ref "R5") (pin "1") (pinfunction "1_1") (pintype "passive"))
      (node (ref "R8") (pin "1") (pinfunction "1_1") (pintype "passive"))
      (node (ref "R9") (pin "1") (pinfunction "1_1") (pintype "passive"))
      (node (ref "RT1") (pin "1") (pinfunction "1_1") (pintype "passive"))
      (node (ref "RT2") (pin "1") (pinfunction "1_1") (pintype "passive"))
      (node (ref "RT3") (pin "1") (pinfunction "1_1") (pintype "passive"))
      (node (ref "SW1") (pin "2-A") (pinfunction "2-A_2-A") (pintype "passive"))
      (node (ref "SW1") (pin "2-B") (pinfunction "2-B_2-B") (pintype "passive"))
      (node (ref "SW2") (pin "1-A") (pinfunction "1-A_1-A") (pintype "passive"))
      (node (ref "SW2") (pin "1-B") (pinfunction "1-B_1-B") (pintype "passive"))
      (node (ref "SW3") (pin "2-A") (pinfunction "2-A_2-A") (pintype "passive"))
      (node (ref "SW3") (pin "2-B") (pinfunction "2-B_2-B") (pintype "passive"))
      (node (ref "SW4") (pin "2-A") (pinfunction "2-A_2-A") (pintype "passive"))
      (node (ref "SW4") (pin "2-B") (pinfunction "2-B_2-B") (pintype "passive"))
      (node (ref "SW5") (pin "2-A") (pinfunction "2-A_2-A") (pintype "passive"))
      (node (ref "SW5") (pin "2-B") (pinfunction "2-B_2-B") (pintype "passive"))
      (node (ref "SW6") (pin "1") (pinfunction "COM_1") (pintype "passive"))
      (node (ref "SW6") (pin "2") (pinfunction "COM_2") (pintype "passive"))
      (node (ref "TP13-GND") (pin "1") (pinfunction "1_1") (pintype "passive"))
      (node (ref "U$1") (pin "1") (pinfunction "GND_1") (pintype "bidirectional"))
      (node (ref "U1") (pin "11") (pinfunction "PGND_11") (pintype "power_in"))
      (node (ref "U1") (pin "PAD") (pinfunction "PAD_PAD") (pintype "power_in"))
      (node (ref "U7") (pin "1") (pinfunction "GND_1") (pintype "power_in"))
      (node (ref "U7") (pin "2") (pinfunction "GND_2") (pintype "power_in"))
      (node (ref "U7") (pin "30") (pinfunction "GND_30") (pintype "power_in"))
      (node (ref "U7") (pin "42") (pinfunction "GND_42") (pintype "power_in"))
      (node (ref "U7") (pin "43") (pinfunction "GND_43") (pintype "power_in"))
      (node (ref "U7") (pin "46") (pinfunction "GND_46") (pintype "power_in"))
      (node (ref "U7") (pin "47") (pinfunction "GND_47") (pintype "power_in"))
      (node (ref "U7") (pin "48") (pinfunction "GND_48") (pintype "power_in"))
      (node (ref "U7") (pin "49") (pinfunction "GND_49") (pintype "power_in"))
      (node (ref "U7") (pin "50") (pinfunction "GND_50") (pintype "power_in"))
      (node (ref "U7") (pin "51") (pinfunction "GND_51") (pintype "power_in"))
      (node (ref "U7") (pin "52") (pinfunction "GND_52") (pintype "power_in"))
      (node (ref "U7") (pin "53") (pinfunction "GND_53") (pintype "power_in"))
      (node (ref "U7") (pin "54") (pinfunction "GND_54") (pintype "power_in"))
      (node (ref "U7") (pin "55") (pinfunction "GND_55") (pintype "power_in"))
      (node (ref "U7") (pin "56") (pinfunction "GND_56") (pintype "power_in"))
      (node (ref "U7") (pin "57") (pinfunction "GND_57") (pintype "power_in"))
      (node (ref "U7") (pin "58") (pinfunction "GND_58") (pintype "power_in"))
      (node (ref "U7") (pin "59") (pinfunction "GND_59") (pintype "power_in"))
      (node (ref "U7") (pin "60") (pinfunction "GND_60") (pintype "power_in"))
      (node (ref "U7") (pin "61") (pinfunction "GND_61") (pintype "power_in"))
      (node (ref "U7") (pin "61_1") (pinfunction "GND_61_1") (pintype "power_in"))
      (node (ref "U7") (pin "61_2") (pinfunction "GND_61_2") (pintype "power_in"))
      (node (ref "U7") (pin "61_3") (pinfunction "GND_61_3") (pintype "power_in"))
      (node (ref "U7") (pin "61_4") (pinfunction "GND_61_4") (pintype "power_in"))
      (node (ref "U7") (pin "61_5") (pinfunction "GND_61_5") (pintype "power_in"))
      (node (ref "U7") (pin "61_6") (pinfunction "GND_61_6") (pintype "power_in"))
      (node (ref "U7") (pin "61_7") (pinfunction "GND_61_7") (pintype "power_in"))
      (node (ref "U7") (pin "61_8") (pinfunction "GND_61_8") (pintype "power_in"))
      (node (ref "U7") (pin "62") (pinfunction "GND_62") (pintype "power_in"))
      (node (ref "U7") (pin "63") (pinfunction "GND_63") (pintype "power_in"))
      (node (ref "U7") (pin "64") (pinfunction "GND_64") (pintype "power_in"))
      (node (ref "U7") (pin "65") (pinfunction "GND_65") (pintype "power_in"))
    )
    (net (code "85") (name "STAT1") (class "Default")
      (node (ref "D1") (pin "4") (pinfunction "STAT_4") (pintype "output"))
      (node (ref "R26") (pin "1") (pinfunction "1_1") (pintype "passive"))
      (node (ref "U7") (pin "5") (pinfunction "IO1_5") (pintype "bidirectional"))
    )
    (net (code "86") (name "STAT2") (class "Default")
      (node (ref "R44") (pin "1") (pinfunction "1_1") (pintype "passive"))
      (node (ref "R46") (pin "2") (pinfunction "2_2") (pintype "passive"))
      (node (ref "U7") (pin "6") (pinfunction "IO2_6") (pintype "bidirectional"))
    )
    (net (code "87") (name "STAT3") (class "Default")
      (node (ref "R45") (pin "1") (pinfunction "1_1") (pintype "passive"))
      (node (ref "R47") (pin "2") (pinfunction "2_2") (pintype "passive"))
      (node (ref "U7") (pin "7") (pinfunction "IO3_7") (pintype "bidirectional"))
    )
    (net (code "88") (name "STAT4") (class "Default")
      (node (ref "D3") (pin "4") (pinfunction "STAT_4") (pintype "output"))
      (node (ref "R27") (pin "1") (pinfunction "1_1") (pintype "passive"))
      (node (ref "U7") (pin "8") (pinfunction "IO4_8") (pintype "bidirectional"))
    )
    (net (code "89") (name "STAT5") (class "Default")
      (node (ref "D4") (pin "4") (pinfunction "STAT_4") (pintype "output"))
      (node (ref "R29") (pin "1") (pinfunction "1_1") (pintype "passive"))
      (node (ref "U7") (pin "9") (pinfunction "IO5_9") (pintype "bidirectional"))
    )
    (net (code "90") (name "STAT6") (class "Default")
      (node (ref "D5") (pin "4") (pinfunction "STAT_4") (pintype "output"))
      (node (ref "R31") (pin "1") (pinfunction "1_1") (pintype "passive"))
      (node (ref "U7") (pin "10") (pinfunction "IO6_10") (pintype "bidirectional"))
    )
    (net (code "91") (name "SW1") (class "Default")
      (node (ref "D1") (pin "3") (pinfunction "CTL_3") (pintype "input"))
      (node (ref "SW1") (pin "COM-A") (pinfunction "COM-A_COM-A") (pintype "passive"))
      (node (ref "SW1") (pin "COM-B") (pinfunction "COM-B_COM-B") (pintype "passive"))
    )
    (net (code "92") (name "SW2") (class "Default")
      (node (ref "R4") (pin "1") (pinfunction "1_1") (pintype "passive"))
      (node (ref "R5") (pin "2") (pinfunction "2_2") (pintype "passive"))
      (node (ref "SW2") (pin "COM-A") (pinfunction "COM-A_COM-A") (pintype "passive"))
      (node (ref "SW2") (pin "COM-B") (pinfunction "COM-B_COM-B") (pintype "passive"))
      (node (ref "U1") (pin "2") (pinfunction "MPPSET_2") (pintype "input"))
    )
    (net (code "93") (name "SW3") (class "Default")
      (node (ref "D3") (pin "3") (pinfunction "CTL_3") (pintype "input"))
      (node (ref "SW3") (pin "COM-A") (pinfunction "COM-A_COM-A") (pintype "passive"))
      (node (ref "SW3") (pin "COM-B") (pinfunction "COM-B_COM-B") (pintype "passive"))
    )
    (net (code "94") (name "SW4") (class "Default")
      (node (ref "D4") (pin "3") (pinfunction "CTL_3") (pintype "input"))
      (node (ref "SW4") (pin "COM-A") (pinfunction "COM-A_COM-A") (pintype "passive"))
      (node (ref "SW4") (pin "COM-B") (pinfunction "COM-B_COM-B") (pintype "passive"))
    )
    (net (code "95") (name "SW5") (class "Default")
      (node (ref "D5") (pin "3") (pinfunction "CTL_3") (pintype "input"))
      (node (ref "SW5") (pin "COM-A") (pinfunction "COM-A_COM-A") (pintype "passive"))
      (node (ref "SW5") (pin "COM-B") (pinfunction "COM-B_COM-B") (pintype "passive"))
    )
    (net (code "96") (name "TEMP_A") (class "Default")
      (node (ref "R38") (pin "1") (pinfunction "1_1") (pintype "passive"))
      (node (ref "RT1") (pin "2") (pinfunction "2_2") (pintype "passive"))
      (node (ref "TP7-TEMP_A") (pin "1") (pinfunction "1_1") (pintype "passive"))
      (node (ref "U7") (pin "11") (pinfunction "IO7_11") (pintype "bidirectional"))
    )
    (net (code "97") (name "TEMP_B") (class "Default")
      (node (ref "R39") (pin "1") (pinfunction "1_1") (pintype "passive"))
      (node (ref "RT2") (pin "2") (pinfunction "2_2") (pintype "passive"))
      (node (ref "TP8-TEMP_B") (pin "1") (pinfunction "1_1") (pintype "passive"))
      (node (ref "U7") (pin "12") (pinfunction "IO8_12") (pintype "bidirectional"))
    )
    (net (code "98") (name "TEMP_C") (class "Default")
      (node (ref "R40") (pin "1") (pinfunction "1_1") (pintype "passive"))
      (node (ref "RT3") (pin "2") (pinfunction "2_2") (pintype "passive"))
      (node (ref "TP9-TEMP_C") (pin "1") (pinfunction "1_1") (pintype "passive"))
      (node (ref "U7") (pin "13") (pinfunction "IO9_13") (pintype "bidirectional"))
    )
    (net (code "99") (name "TS-ESP") (class "Default")
      (node (ref "TP3-TS") (pin "1") (pinfunction "1_1") (pintype "passive"))
      (node (ref "U1") (pin "4") (pinfunction "TS_4") (pintype "input"))
      (node (ref "U7") (pin "14") (pinfunction "IO10_14") (pintype "bidirectional"))
    )
    (net (code "100") (name "UART-ESP_EN") (class "Default")
      (node (ref "C21") (pin "2") (pinfunction "2_2") (pintype "passive"))
      (node (ref "C22") (pin "1") (pinfunction "1_1") (pintype "passive"))
      (node (ref "Q6") (pin "3") (pinfunction "C_3") (pintype "passive"))
      (node (ref "R37") (pin "1") (pinfunction "1_1") (pintype "passive"))
      (node (ref "SW6") (pin "3") (pinfunction "NO_3") (pintype "passive"))
      (node (ref "SW6") (pin "4") (pinfunction "NO_4") (pintype "passive"))
      (node (ref "U7") (pin "45") (pinfunction "EN_45") (pintype "input"))
    )
    (net (code "101") (name "UART-ESP_IO0") (class "Default")
      (node (ref "Q7") (pin "3") (pinfunction "C_3") (pintype "passive"))
      (node (ref "U7") (pin "4") (pinfunction "IO0_4") (pintype "bidirectional"))
    )
    (net (code "102") (name "UART_RXD-ESP_TXD") (class "Default")
      (node (ref "U5") (pin "25") (pinfunction "RXD_25") (pintype "input"))
      (node (ref "U7") (pin "39") (pinfunction "TXD0_39") (pintype "bidirectional"))
    )
    (net (code "103") (name "UART_TXD-ESP_RXD") (class "Default")
      (node (ref "U5") (pin "26") (pinfunction "TXD_26") (pintype "output"))
      (node (ref "U7") (pin "40") (pinfunction "RXD0_40") (pintype "bidirectional"))
    )
    (net (code "104") (name "unconnected-(D8-DOUT-Pad2)") (class "Default")
      (node (ref "D8") (pin "2") (pinfunction "DOUT_2") (pintype "output"))
    )
    (net (code "105") (name "unconnected-(J1-CC1-PadA5)") (class "Default")
      (node (ref "J1") (pin "A5") (pinfunction "CC1_A5") (pintype "passive"))
    )
    (net (code "106") (name "unconnected-(J1-CC2-PadB5)") (class "Default")
      (node (ref "J1") (pin "B5") (pinfunction "CC2_B5") (pintype "passive"))
    )
    (net (code "107") (name "unconnected-(J3-ID-Pad4)") (class "Default")
      (node (ref "J3") (pin "4") (pinfunction "ID_4") (pintype "bidirectional"))
    )
    (net (code "108") (name "unconnected-(Q3-D-PadPAD)") (class "Default")
      (node (ref "Q3") (pin "PAD") (pinfunction "D_PAD") (pintype "passive"))
    )
    (net (code "109") (name "unconnected-(Q4-D-PadPAD)") (class "Default")
      (node (ref "Q4") (pin "PAD") (pinfunction "D_PAD") (pintype "passive"))
    )
    (net (code "110") (name "unconnected-(Q5-D-PadPAD)") (class "Default")
      (node (ref "Q5") (pin "PAD") (pinfunction "D_PAD") (pintype "passive"))
    )
    (net (code "111") (name "unconnected-(SW2-Pad2-A)") (class "Default")
      (node (ref "SW2") (pin "2-A") (pinfunction "2-A_2-A") (pintype "passive"))
    )
    (net (code "112") (name "unconnected-(SW2-Pad2-B)") (class "Default")
      (node (ref "SW2") (pin "2-B") (pinfunction "2-B_2-B") (pintype "passive"))
    )
    (net (code "113") (name "unconnected-(U$1-V_OUT2-PadTAB)") (class "Default")
      (node (ref "U$1") (pin "TAB") (pinfunction "V_OUT2_TAB") (pintype "bidirectional"))
    )
    (net (code "114") (name "unconnected-(U5-CHR0-Pad15)") (class "Default")
      (node (ref "U5") (pin "15") (pinfunction "CHR0_15") (pintype "output"))
    )
    (net (code "115") (name "unconnected-(U5-CHR1-Pad14)") (class "Default")
      (node (ref "U5") (pin "14") (pinfunction "CHR1_14") (pintype "output"))
    )
    (net (code "116") (name "unconnected-(U5-CHREN-Pad13)") (class "Default")
      (node (ref "U5") (pin "13") (pinfunction "CHREN_13") (pintype "output"))
    )
    (net (code "117") (name "unconnected-(U5-CTS-Pad23)") (class "Default")
      (node (ref "U5") (pin "23") (pinfunction "CTS_23") (pintype "input"))
    )
    (net (code "118") (name "unconnected-(U5-DCD-Pad1)") (class "Default")
      (node (ref "U5") (pin "1") (pinfunction "DCD_1") (pintype "input"))
    )
    (net (code "119") (name "unconnected-(U5-DSR-Pad27)") (class "Default")
      (node (ref "U5") (pin "27") (pinfunction "DSR_27") (pintype "input"))
    )
    (net (code "120") (name "unconnected-(U5-GPIO.2{slash}RS485-Pad17)") (class "Default")
      (node (ref "U5") (pin "17") (pinfunction "GPIO.2/RS485_17") (pintype "bidirectional"))
    )
    (net (code "121") (name "unconnected-(U5-GPIO.3{slash}WAKEUP-Pad16)") (class "Default")
      (node (ref "U5") (pin "16") (pinfunction "GPIO.3/WAKEUP_16") (pintype "bidirectional"))
    )
    (net (code "122") (name "unconnected-(U5-GPIO.4-Pad22)") (class "Default")
      (node (ref "U5") (pin "22") (pinfunction "GPIO.4_22") (pintype "bidirectional"))
    )
    (net (code "123") (name "unconnected-(U5-GPIO.5-Pad21)") (class "Default")
      (node (ref "U5") (pin "21") (pinfunction "GPIO.5_21") (pintype "bidirectional"))
    )
    (net (code "124") (name "unconnected-(U5-GPIO.6-Pad20)") (class "Default")
      (node (ref "U5") (pin "20") (pinfunction "GPIO.6_20") (pintype "bidirectional"))
    )
    (net (code "125") (name "unconnected-(U5-NC-Pad10)") (class "Default")
      (node (ref "U5") (pin "10") (pinfunction "NC_10") (pintype "no_connect"))
    )
    (net (code "126") (name "unconnected-(U5-RI{slash}CLK-Pad2)") (class "Default")
      (node (ref "U5") (pin "2") (pinfunction "RI/CLK_2") (pintype "bidirectional"))
    )
    (net (code "127") (name "unconnected-(U5-SUSPEND-Pad12)") (class "Default")
      (node (ref "U5") (pin "12") (pinfunction "SUSPEND_12") (pintype "output"))
    )
    (net (code "128") (name "unconnected-(U5-~{RST}-Pad9)") (class "Default")
      (node (ref "U5") (pin "9") (pinfunction "~{RST}_9") (pintype "input"))
    )
    (net (code "129") (name "unconnected-(U5-~{SUSPEND}-Pad11)") (class "Default")
      (node (ref "U5") (pin "11") (pinfunction "~{SUSPEND}_11") (pintype "output"))
    )
    (net (code "130") (name "unconnected-(U7-NC-Pad27)") (class "Default")
      (node (ref "U7") (pin "27") (pinfunction "NC_27") (pintype "no_connect"))
    )
  )
)
